# XMICRO-6502_V2_4.net
KiCad netlist of a schematic drawn in EAGLE
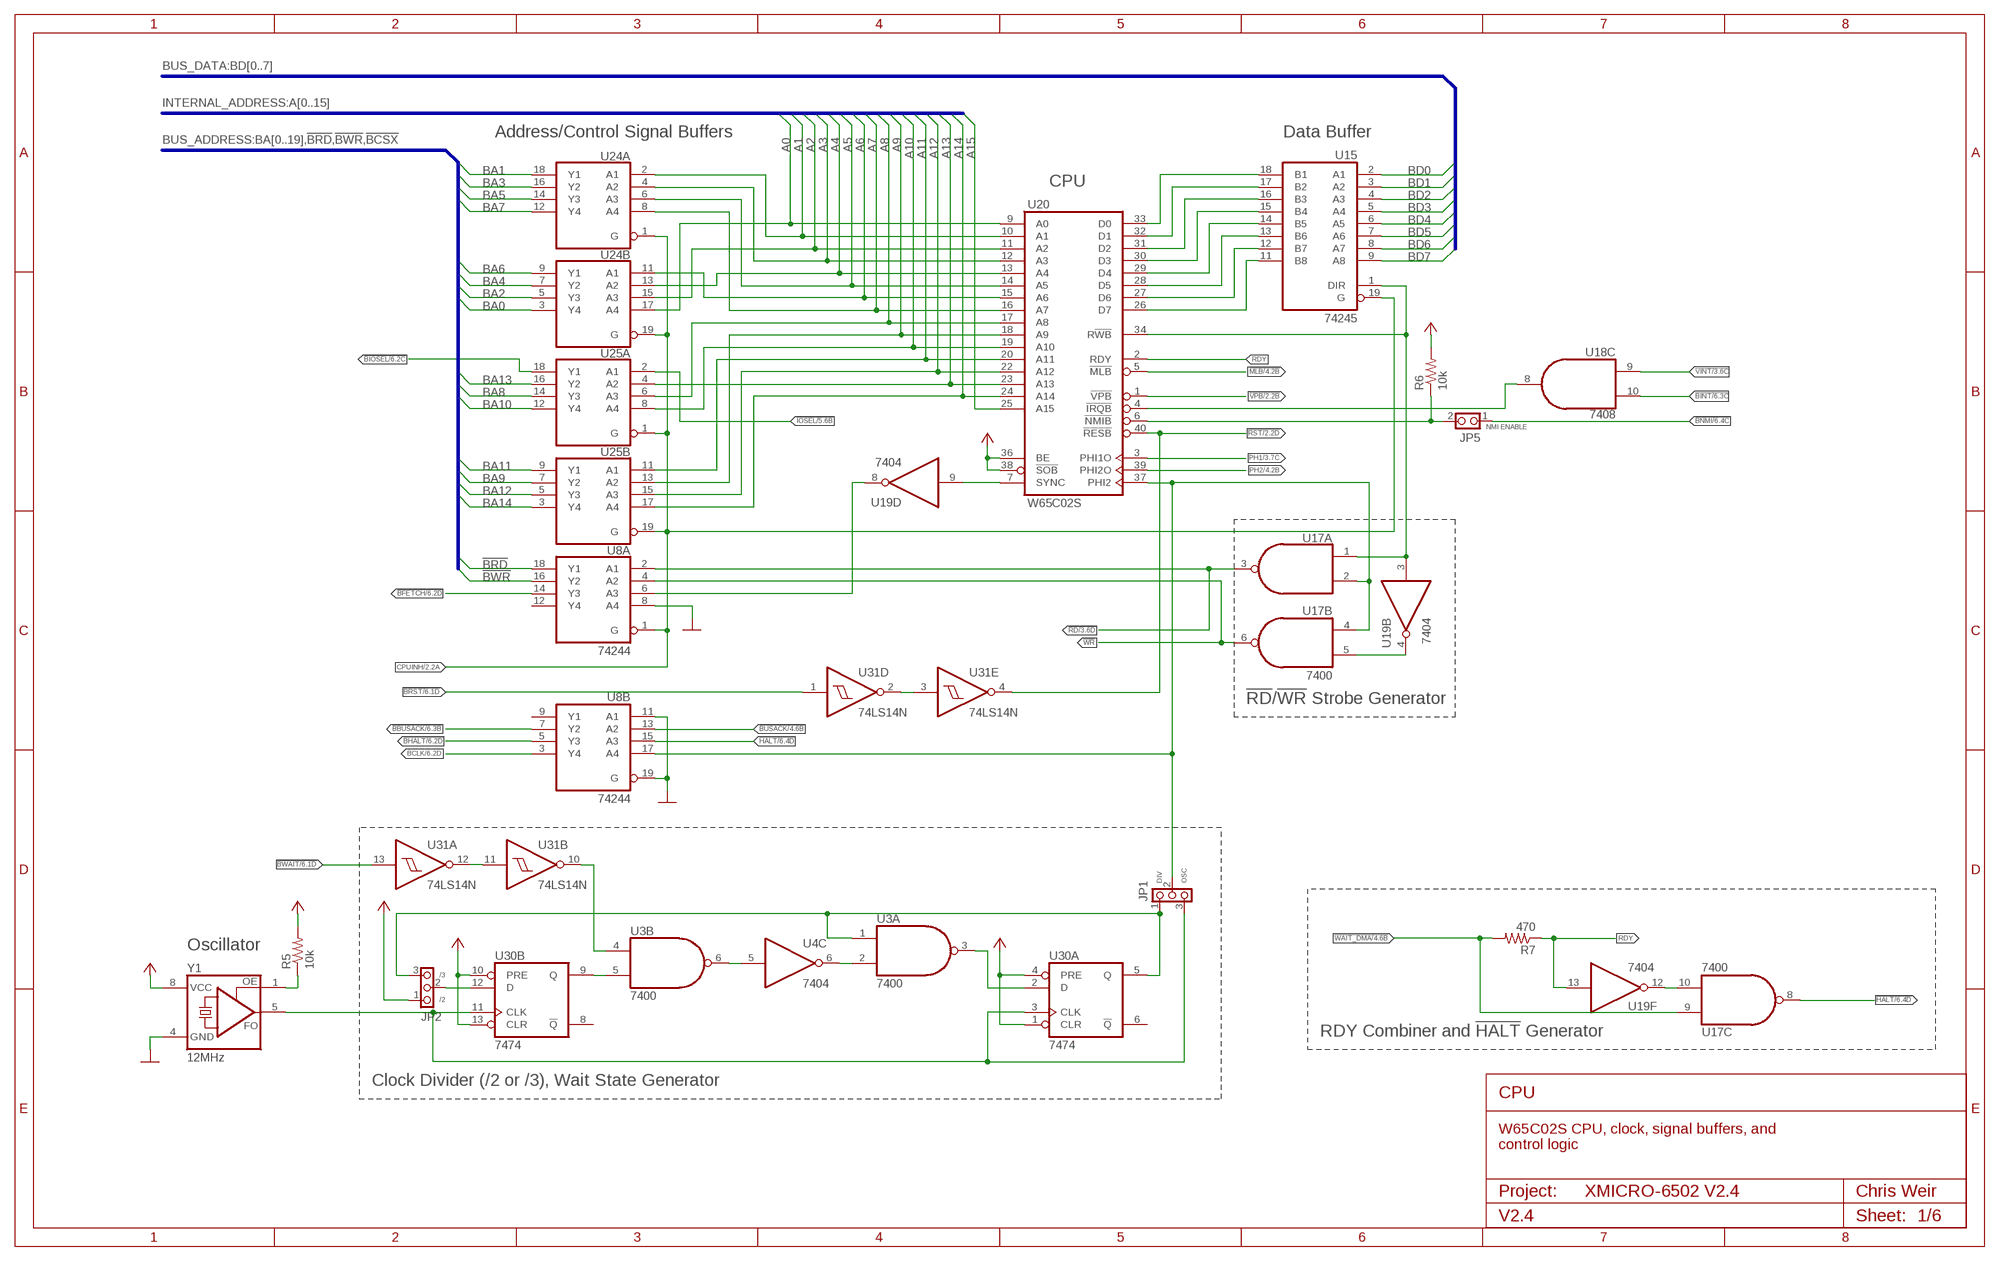
[diagram p0: schematic, sheet 1]
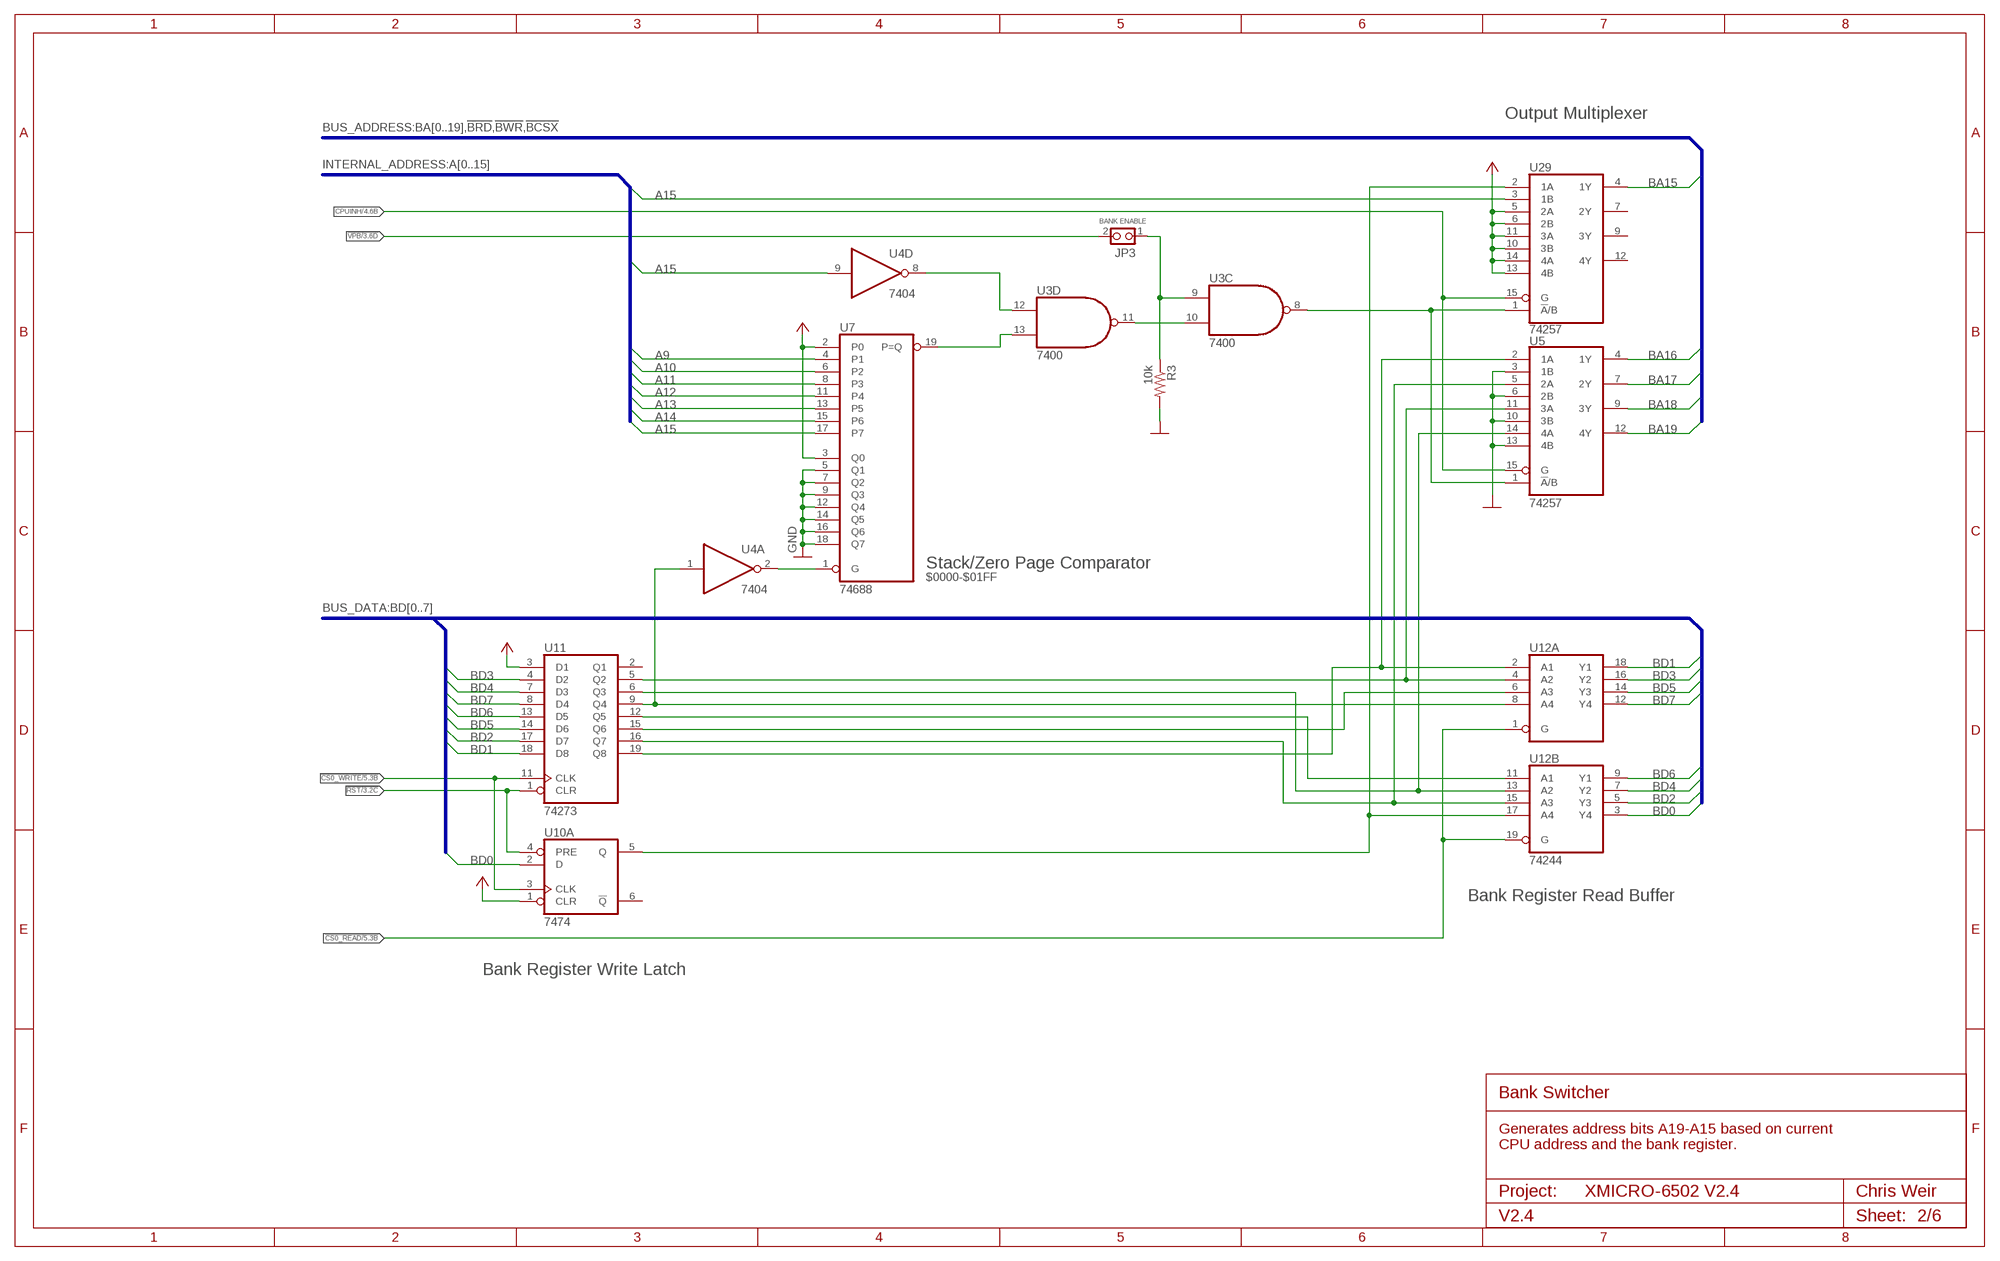
[diagram p1: schematic, sheet 2]
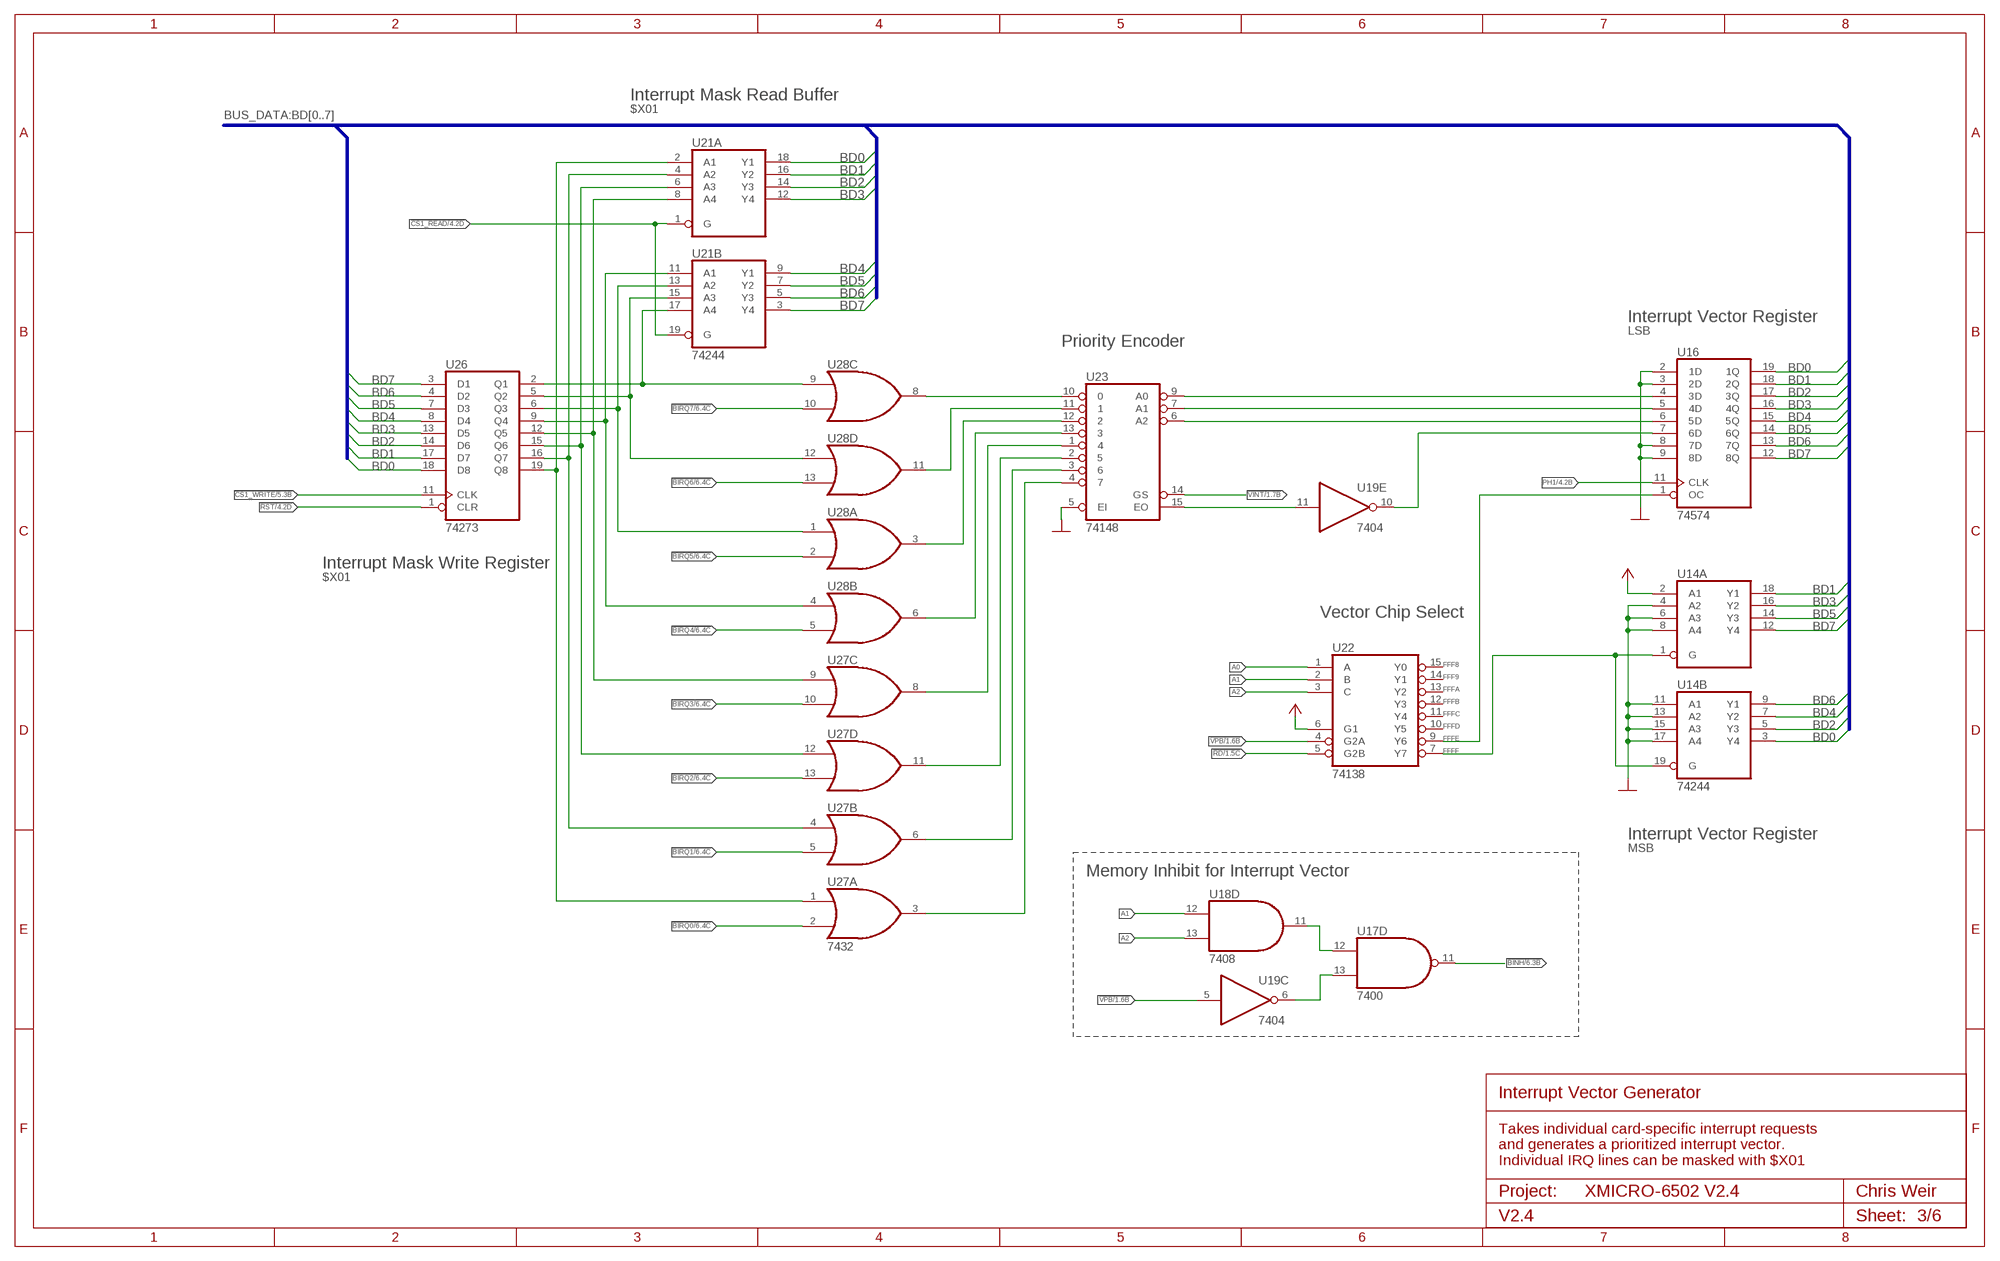
[diagram p2: schematic, sheet 3]
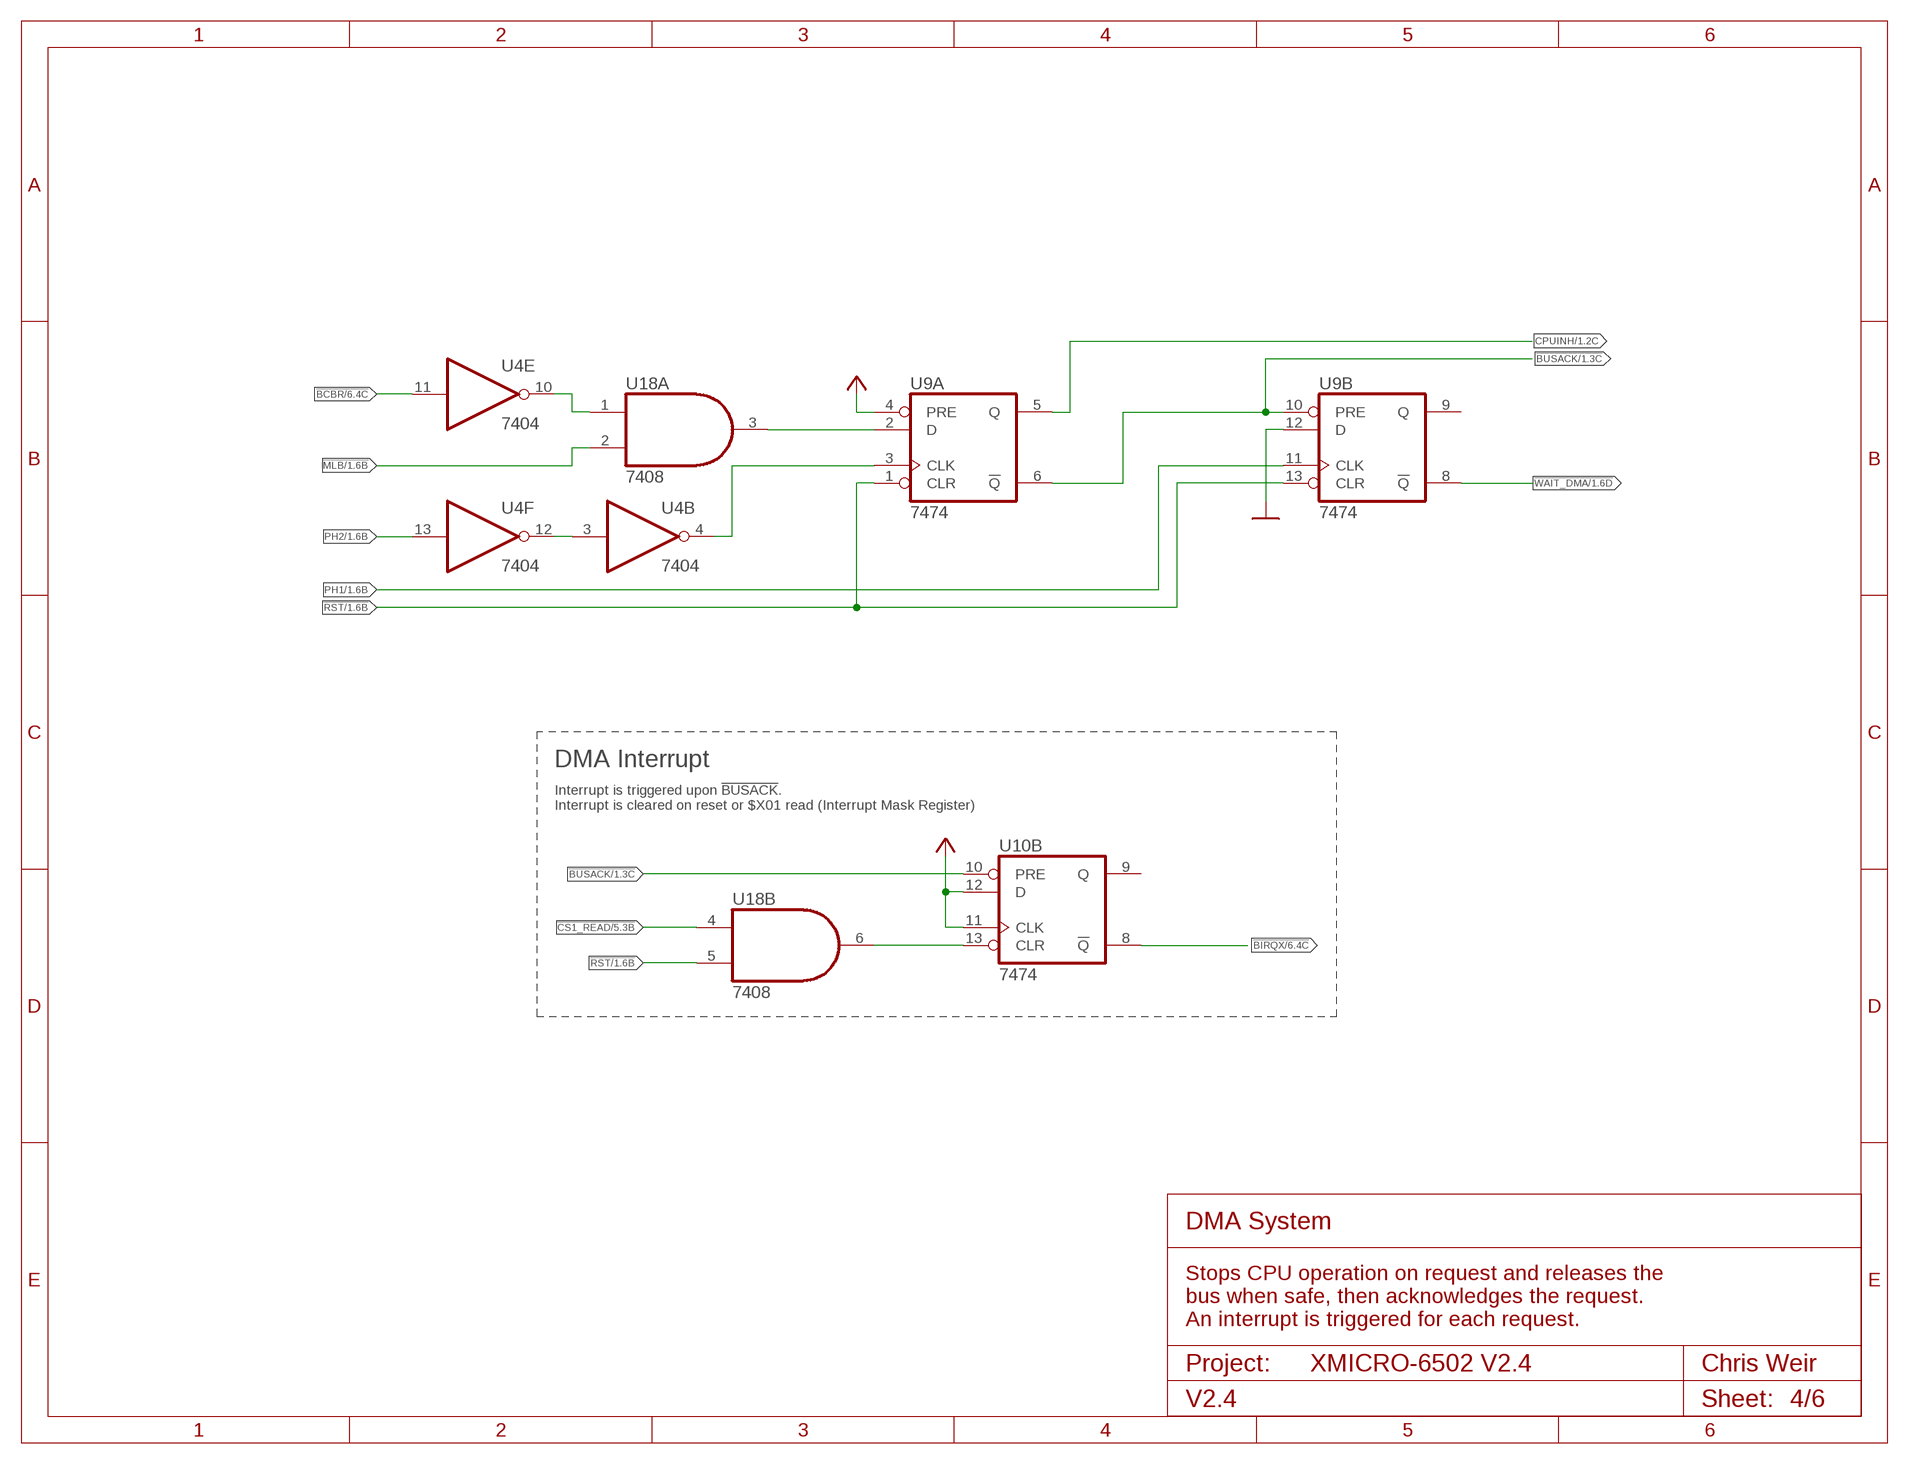
[diagram p3: schematic, sheet 4]
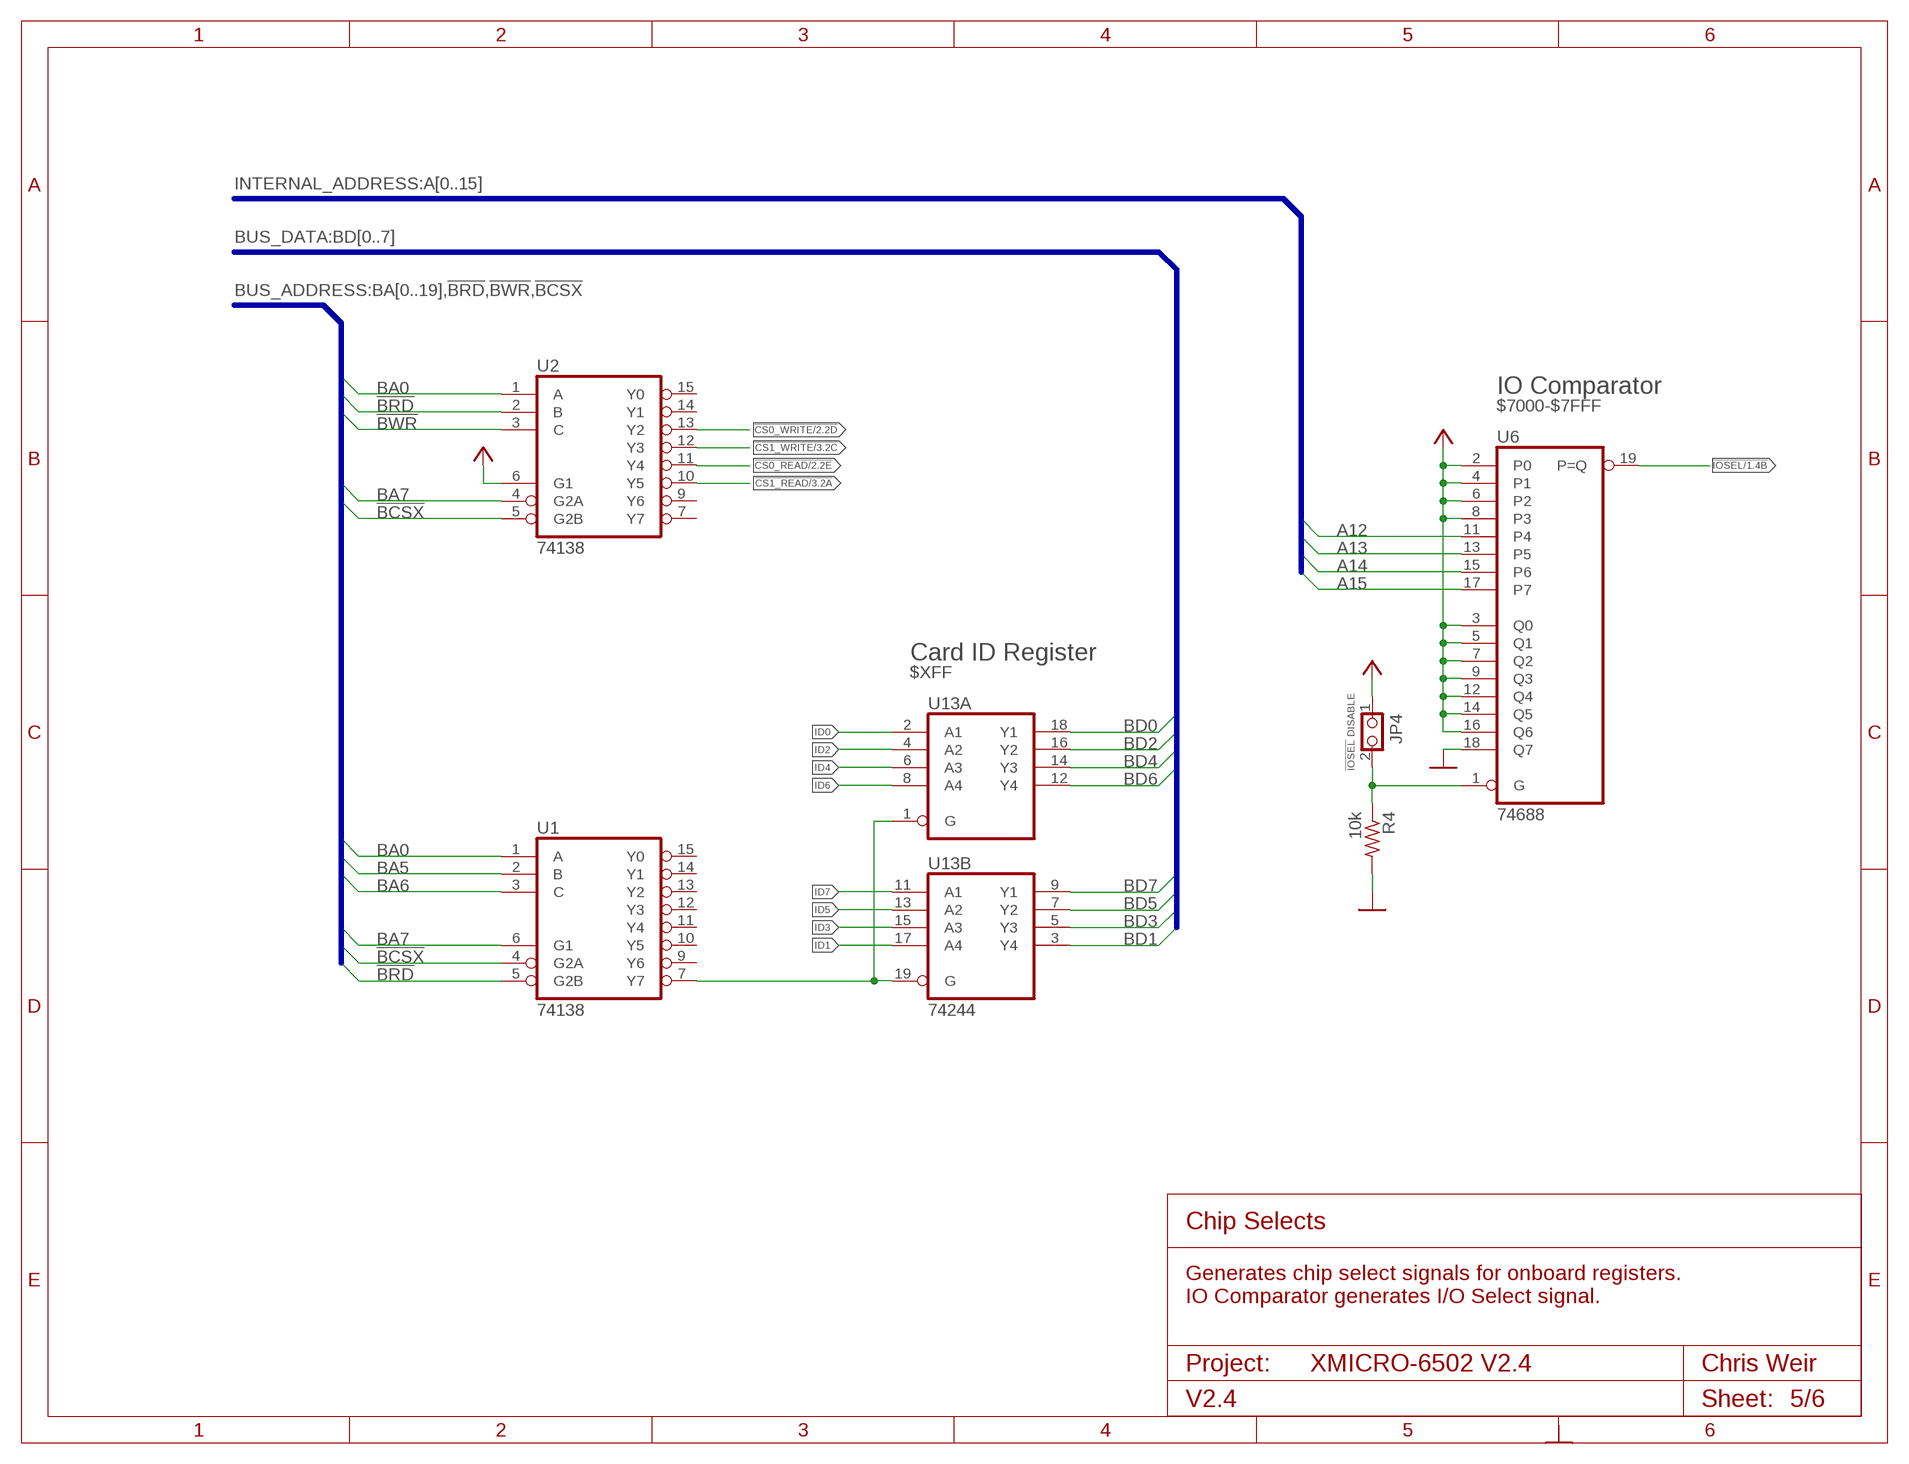
[diagram p4: schematic, sheet 5]
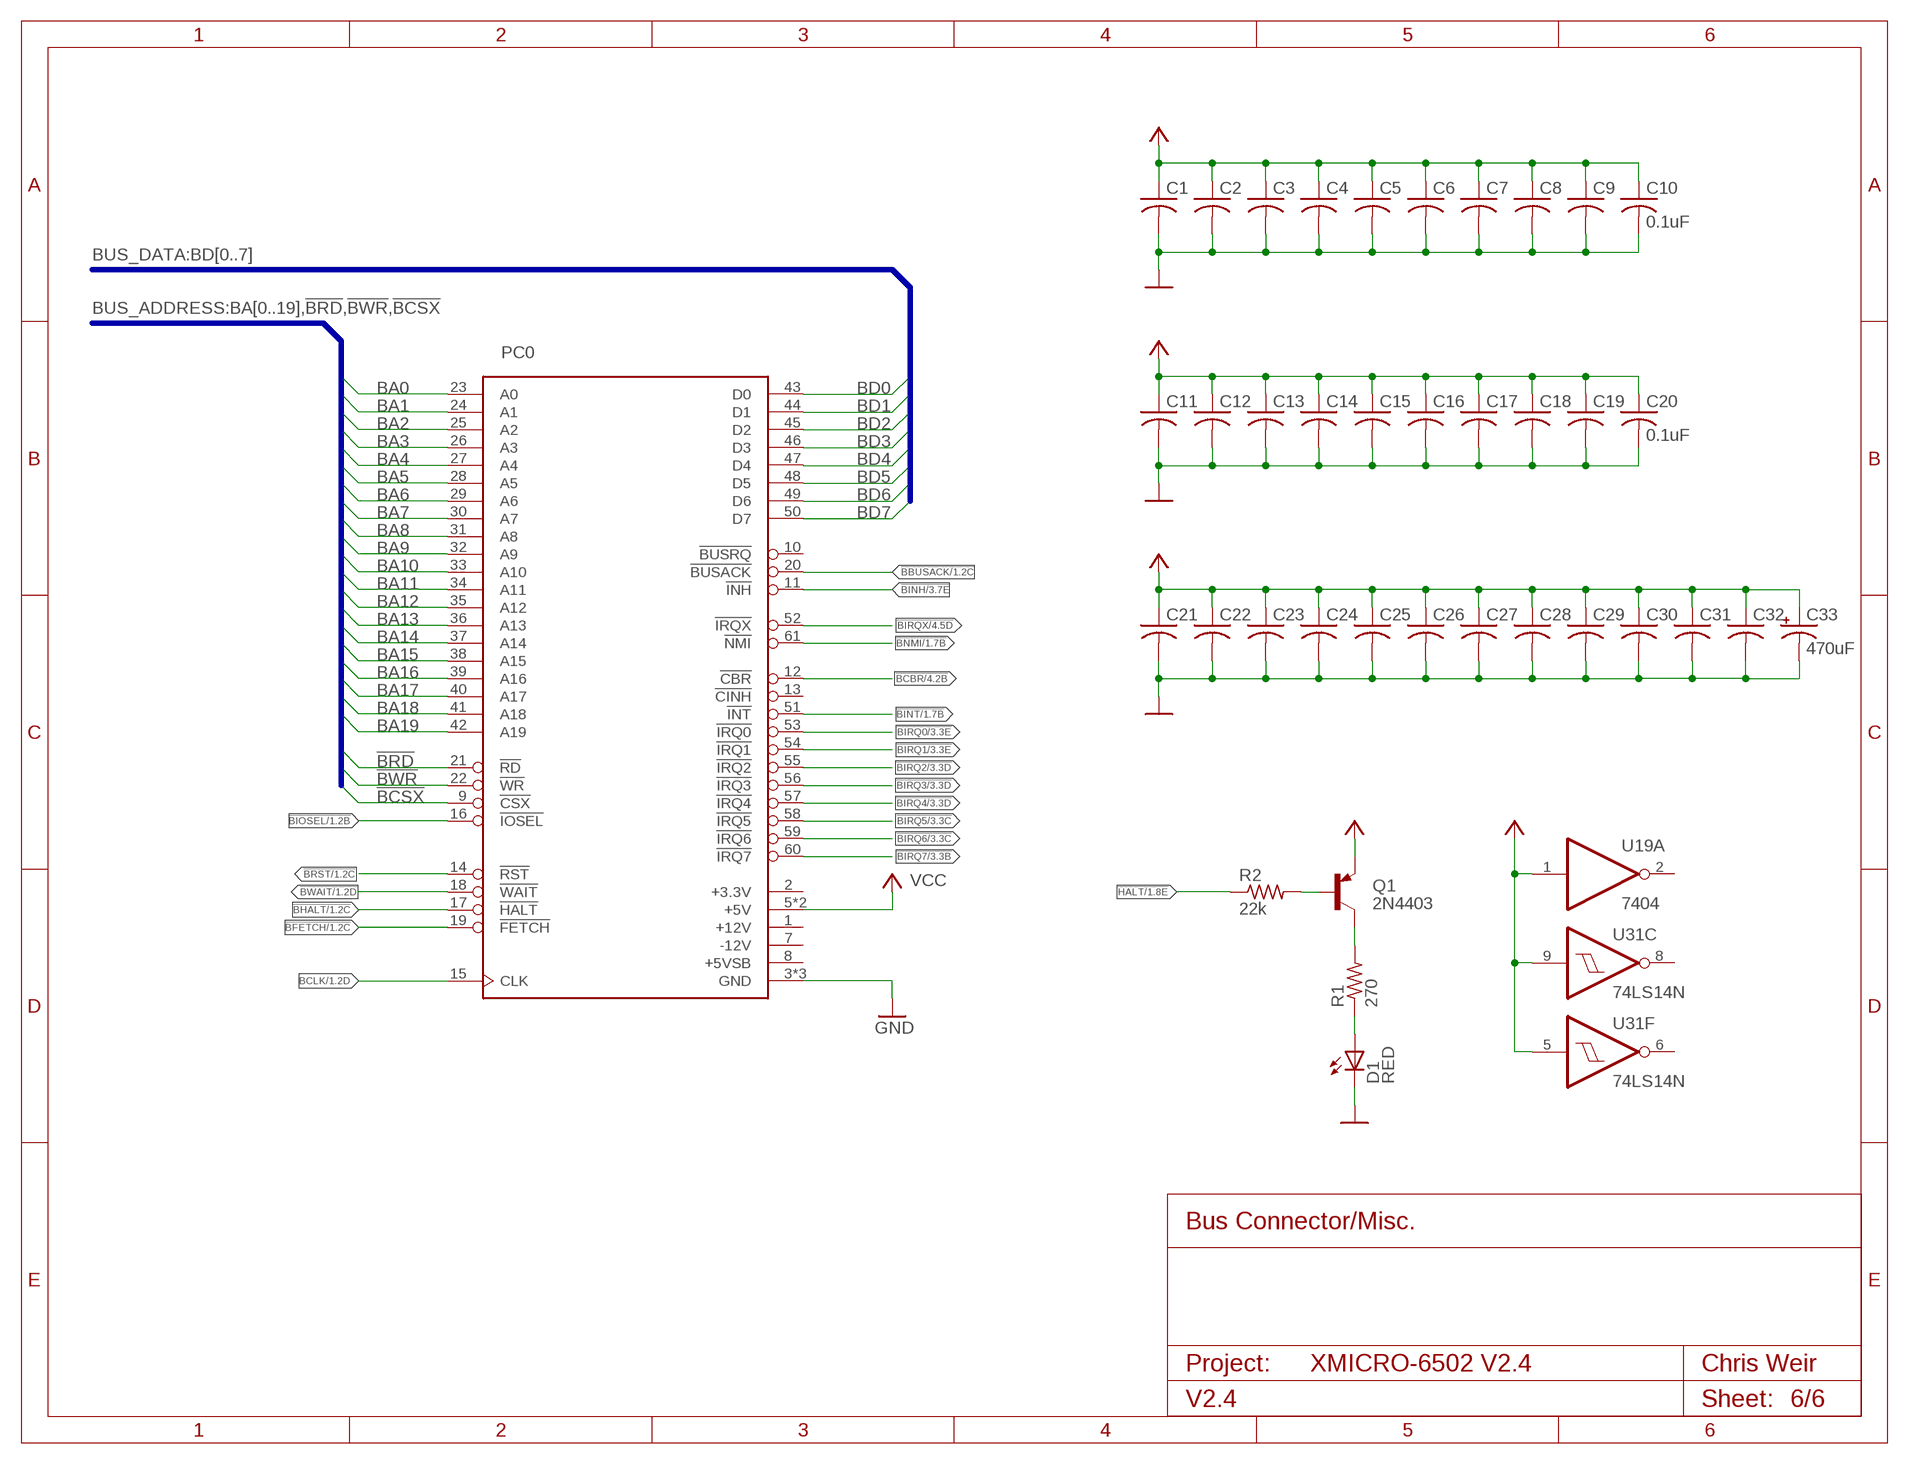
[diagram p5: schematic, sheet 6]

(export (version "E")
  (design (tool "Eeschema 10.0.6"))
  (components
    (comp (ref "C1")
      (value "0.1uF")
      (footprint "eagle-import:C025-024X044")
      (libsource (lib "eagle-import") (part "C-US025-024X044"))
    )
    (comp (ref "C2")
      (value "0.1uF")
      (footprint "eagle-import:C025-024X044")
      (libsource (lib "eagle-import") (part "C-US025-024X044"))
    )
    (comp (ref "C3")
      (value "0.1uF")
      (footprint "eagle-import:C025-024X044")
      (libsource (lib "eagle-import") (part "C-US025-024X044"))
    )
    (comp (ref "C4")
      (value "0.1uF")
      (footprint "eagle-import:C025-024X044")
      (libsource (lib "eagle-import") (part "C-US025-024X044"))
    )
    (comp (ref "C5")
      (value "0.1uF")
      (footprint "eagle-import:C025-024X044")
      (libsource (lib "eagle-import") (part "C-US025-024X044"))
    )
    (comp (ref "C6")
      (value "0.1uF")
      (footprint "eagle-import:C025-024X044")
      (libsource (lib "eagle-import") (part "C-US025-024X044"))
    )
    (comp (ref "C7")
      (value "0.1uF")
      (footprint "eagle-import:C025-024X044")
      (libsource (lib "eagle-import") (part "C-US025-024X044"))
    )
    (comp (ref "C8")
      (value "0.1uF")
      (footprint "eagle-import:C025-024X044")
      (libsource (lib "eagle-import") (part "C-US025-024X044"))
    )
    (comp (ref "C9")
      (value "0.1uF")
      (footprint "eagle-import:C025-024X044")
      (libsource (lib "eagle-import") (part "C-US025-024X044"))
    )
    (comp (ref "C10")
      (value "0.1uF")
      (footprint "eagle-import:C025-024X044")
      (libsource (lib "eagle-import") (part "C-US025-024X044"))
    )
    (comp (ref "C11")
      (value "0.1uF")
      (footprint "eagle-import:C025-024X044")
      (libsource (lib "eagle-import") (part "C-US025-024X044"))
    )
    (comp (ref "C12")
      (value "0.1uF")
      (footprint "eagle-import:C025-024X044")
      (libsource (lib "eagle-import") (part "C-US025-024X044"))
    )
    (comp (ref "C13")
      (value "0.1uF")
      (footprint "eagle-import:C025-024X044")
      (libsource (lib "eagle-import") (part "C-US025-024X044"))
    )
    (comp (ref "C14")
      (value "0.1uF")
      (footprint "eagle-import:C025-024X044")
      (libsource (lib "eagle-import") (part "C-US025-024X044"))
    )
    (comp (ref "C15")
      (value "0.1uF")
      (footprint "eagle-import:C025-024X044")
      (libsource (lib "eagle-import") (part "C-US025-024X044"))
    )
    (comp (ref "C16")
      (value "0.1uF")
      (footprint "eagle-import:C025-024X044")
      (libsource (lib "eagle-import") (part "C-US025-024X044"))
    )
    (comp (ref "C17")
      (value "0.1uF")
      (footprint "eagle-import:C025-024X044")
      (libsource (lib "eagle-import") (part "C-US025-024X044"))
    )
    (comp (ref "C18")
      (value "0.1uF")
      (footprint "eagle-import:C025-024X044")
      (libsource (lib "eagle-import") (part "C-US025-024X044"))
    )
    (comp (ref "C19")
      (value "0.1uF")
      (footprint "eagle-import:C025-024X044")
      (libsource (lib "eagle-import") (part "C-US025-024X044"))
    )
    (comp (ref "C20")
      (value "0.1uF")
      (footprint "eagle-import:C025-024X044")
      (libsource (lib "eagle-import") (part "C-US025-024X044"))
    )
    (comp (ref "C21")
      (value "0.1uF")
      (footprint "eagle-import:C025-024X044")
      (libsource (lib "eagle-import") (part "C-US025-024X044"))
    )
    (comp (ref "C22")
      (value "0.1uF")
      (footprint "eagle-import:C025-024X044")
      (libsource (lib "eagle-import") (part "C-US025-024X044"))
    )
    (comp (ref "C23")
      (value "0.1uF")
      (footprint "eagle-import:C025-024X044")
      (libsource (lib "eagle-import") (part "C-US025-024X044"))
    )
    (comp (ref "C24")
      (value "0.1uF")
      (footprint "eagle-import:C025-024X044")
      (libsource (lib "eagle-import") (part "C-US025-024X044"))
    )
    (comp (ref "C25")
      (value "0.1uF")
      (footprint "eagle-import:C025-024X044")
      (libsource (lib "eagle-import") (part "C-US025-024X044"))
    )
    (comp (ref "C26")
      (value "0.1uF")
      (footprint "eagle-import:C025-024X044")
      (libsource (lib "eagle-import") (part "C-US025-024X044"))
    )
    (comp (ref "C27")
      (value "0.1uF")
      (footprint "eagle-import:C025-024X044")
      (libsource (lib "eagle-import") (part "C-US025-024X044"))
    )
    (comp (ref "C28")
      (value "0.1uF")
      (footprint "eagle-import:C025-024X044")
      (libsource (lib "eagle-import") (part "C-US025-024X044"))
    )
    (comp (ref "C29")
      (value "0.1uF")
      (footprint "eagle-import:C025-024X044")
      (libsource (lib "eagle-import") (part "C-US025-024X044"))
    )
    (comp (ref "C30")
      (value "0.1uF")
      (footprint "eagle-import:C025-024X044")
      (libsource (lib "eagle-import") (part "C-US025-024X044"))
    )
    (comp (ref "C31")
      (value "0.1uF")
      (footprint "eagle-import:C025-024X044")
      (libsource (lib "eagle-import") (part "C-US025-024X044"))
    )
    (comp (ref "C32")
      (value "0.1uF")
      (footprint "eagle-import:C025-024X044")
      (libsource (lib "eagle-import") (part "C-US025-024X044"))
    )
    (comp (ref "C33")
      (value "470uF")
      (footprint "eagle-import:C-10-5")
      (libsource (lib "eagle-import") (part "CPOL-US-10-5"))
    )
    (comp (ref "D1")
      (value "RED")
      (footprint "eagle-import:LED5MM")
      (libsource (lib "eagle-import") (part "LED5MM"))
    )
    (comp (ref "PC0")
      (value "XMICRO-BUS-EDGE62M")
      (footprint "eagle-import:EDGE62M")
      (libsource (lib "eagle-import") (part "XMICRO-BUS-EDGE62M"))
    )
    (comp (ref "Q1")
      (value "2N4403")
      (footprint "eagle-import:TO92")
      (libsource (lib "eagle-import") (part "TRANSISTOR-PNP-2N4403"))
    )
    (comp (ref "R1")
      (value "270")
      (footprint "eagle-import:0207_10")
      (libsource (lib "eagle-import") (part "R-US_0207/10"))
    )
    (comp (ref "R2")
      (value "22k")
      (footprint "eagle-import:0207_10")
      (libsource (lib "eagle-import") (part "R-US_0207/10"))
    )
    (comp (ref "U19")
      (value "7404")
      (footprint "eagle-import:DIL14")
      (libsource (lib "eagle-import") (part "7404NLS"))
    )
    (comp (ref "U31")
      (value "74LS14N")
      (footprint "eagle-import:DIL14")
      (libsource (lib "eagle-import") (part "7414NLS"))
    )
    (comp (ref "JP3")
      (value "PINHD-1X2THRU")
      (footprint "eagle-import:1X02")
      (libsource (lib "eagle-import") (part "PINHD-1X2THRU"))
    )
    (comp (ref "R3")
      (value "10k")
      (footprint "eagle-import:0207_10")
      (libsource (lib "eagle-import") (part "R-US_0207/10"))
    )
    (comp (ref "U3")
      (value "7400")
      (footprint "eagle-import:DIL14")
      (libsource (lib "eagle-import") (part "7400NLS"))
    )
    (comp (ref "U4")
      (value "7404")
      (footprint "eagle-import:DIL14")
      (libsource (lib "eagle-import") (part "7404NLS"))
    )
    (comp (ref "U5")
      (value "74257")
      (footprint "eagle-import:DIL16")
      (libsource (lib "eagle-import") (part "74257NLS"))
    )
    (comp (ref "U7")
      (value "74688")
      (footprint "eagle-import:DIL20")
      (libsource (lib "eagle-import") (part "74688NLS"))
    )
    (comp (ref "U10")
      (value "7474")
      (footprint "eagle-import:DIL14")
      (libsource (lib "eagle-import") (part "7474NLS"))
    )
    (comp (ref "U11")
      (value "74273")
      (footprint "eagle-import:DIL20")
      (libsource (lib "eagle-import") (part "74273N"))
    )
    (comp (ref "U12")
      (value "74244")
      (footprint "eagle-import:DIL20")
      (libsource (lib "eagle-import") (part "74244NLS"))
    )
    (comp (ref "U29")
      (value "74257")
      (footprint "eagle-import:DIL16")
      (libsource (lib "eagle-import") (part "74257NLS"))
    )
    (comp (ref "JP4")
      (value "PINHD-1X2THRU")
      (footprint "eagle-import:1X02")
      (libsource (lib "eagle-import") (part "PINHD-1X2THRU"))
    )
    (comp (ref "R4")
      (value "10k")
      (footprint "eagle-import:0207_10")
      (libsource (lib "eagle-import") (part "R-US_0207/10"))
    )
    (comp (ref "U1")
      (value "74138")
      (footprint "eagle-import:DIL16")
      (libsource (lib "eagle-import") (part "74138NLS"))
    )
    (comp (ref "U2")
      (value "74138")
      (footprint "eagle-import:DIL16")
      (libsource (lib "eagle-import") (part "74138NLS"))
    )
    (comp (ref "U6")
      (value "74688")
      (footprint "eagle-import:DIL20")
      (libsource (lib "eagle-import") (part "74688NLS"))
    )
    (comp (ref "U13")
      (value "74244")
      (footprint "eagle-import:DIL20")
      (libsource (lib "eagle-import") (part "74244NLS"))
    )
    (comp (ref "U14")
      (value "74244")
      (footprint "eagle-import:DIL20")
      (libsource (lib "eagle-import") (part "74244NLS"))
    )
    (comp (ref "U16")
      (value "74574")
      (footprint "eagle-import:DIL20")
      (libsource (lib "eagle-import") (part "74574NHC"))
    )
    (comp (ref "U17")
      (value "7400")
      (footprint "eagle-import:DIL14")
      (libsource (lib "eagle-import") (part "7400NLS"))
    )
    (comp (ref "U18")
      (value "7408")
      (footprint "eagle-import:DIL14")
      (libsource (lib "eagle-import") (part "7408NLS"))
    )
    (comp (ref "U21")
      (value "74244")
      (footprint "eagle-import:DIL20")
      (libsource (lib "eagle-import") (part "74244NLS"))
    )
    (comp (ref "U22")
      (value "74138")
      (footprint "eagle-import:DIL16")
      (libsource (lib "eagle-import") (part "74138NLS"))
    )
    (comp (ref "U23")
      (value "74148")
      (footprint "eagle-import:DIL16")
      (libsource (lib "eagle-import") (part "74148NLS"))
    )
    (comp (ref "U26")
      (value "74273")
      (footprint "eagle-import:DIL20")
      (libsource (lib "eagle-import") (part "74273N"))
    )
    (comp (ref "U27")
      (value "7432")
      (footprint "eagle-import:DIL14")
      (libsource (lib "eagle-import") (part "7432NLS"))
    )
    (comp (ref "U28")
      (value "7432")
      (footprint "eagle-import:DIL14")
      (libsource (lib "eagle-import") (part "7432NLS"))
    )
    (comp (ref "U9")
      (value "7474")
      (footprint "eagle-import:DIL14")
      (libsource (lib "eagle-import") (part "7474NLS"))
    )
    (comp (ref "JP1")
      (value "PINHD1X3THRU")
      (footprint "eagle-import:1X03")
      (libsource (lib "eagle-import") (part "PINHD1X3THRU"))
    )
    (comp (ref "JP2")
      (value "PINHD1X3THRU")
      (footprint "eagle-import:1X03")
      (libsource (lib "eagle-import") (part "PINHD1X3THRU"))
    )
    (comp (ref "JP5")
      (value "PINHD-1X2THRU")
      (footprint "eagle-import:1X02")
      (libsource (lib "eagle-import") (part "PINHD-1X2THRU"))
    )
    (comp (ref "R5")
      (value "10k")
      (footprint "eagle-import:0207_10")
      (libsource (lib "eagle-import") (part "R-US_0207/10"))
    )
    (comp (ref "R6")
      (value "10k")
      (footprint "eagle-import:0207_10")
      (libsource (lib "eagle-import") (part "R-US_0207/10"))
    )
    (comp (ref "R7")
      (value "470")
      (footprint "eagle-import:0207_10")
      (libsource (lib "eagle-import") (part "R-US_0207/10"))
    )
    (comp (ref "U8")
      (value "74244")
      (footprint "eagle-import:DIL20")
      (libsource (lib "eagle-import") (part "74244NLS"))
    )
    (comp (ref "U15")
      (value "74245")
      (footprint "eagle-import:DIL20")
      (libsource (lib "eagle-import") (part "74245NLS"))
    )
    (comp (ref "U20")
      (value "W65C02S")
      (footprint "eagle-import:DIL40")
      (libsource (lib "eagle-import") (part "W65C02P"))
    )
    (comp (ref "U24")
      (value "74244")
      (footprint "eagle-import:DIL20")
      (libsource (lib "eagle-import") (part "74244NLS"))
    )
    (comp (ref "U25")
      (value "74244")
      (footprint "eagle-import:DIL20")
      (libsource (lib "eagle-import") (part "74244NLS"))
    )
    (comp (ref "U30")
      (value "7474")
      (footprint "eagle-import:DIL14")
      (libsource (lib "eagle-import") (part "7474NLS"))
    )
    (comp (ref "Y1")
      (value "12MHz")
      (footprint "eagle-import:DIL08S")
      (libsource (lib "eagle-import") (part "OSC-OE"))
    )
  )
  (nets
    (net (code "105") (name "A0") (class "Default")
      (node (ref "U20") (pin "9") (pinfunction "A0_9") (pintype "output"))
      (node (ref "U22") (pin "1") (pinfunction "A_1") (pintype "input"))
      (node (ref "U24") (pin "17") (pinfunction "A4_17") (pintype "input"))
    )
    (net (code "106") (name "A1") (class "Default")
      (node (ref "U18") (pin "12") (pinfunction "I0_12") (pintype "input"))
      (node (ref "U20") (pin "10") (pinfunction "A1_10") (pintype "output"))
      (node (ref "U22") (pin "2") (pinfunction "B_2") (pintype "input"))
      (node (ref "U24") (pin "2") (pinfunction "A1_2") (pintype "input"))
    )
    (net (code "107") (name "A2") (class "Default")
      (node (ref "U18") (pin "13") (pinfunction "I1_13") (pintype "input"))
      (node (ref "U20") (pin "11") (pinfunction "A2_11") (pintype "output"))
      (node (ref "U22") (pin "3") (pinfunction "C_3") (pintype "input"))
      (node (ref "U24") (pin "15") (pinfunction "A3_15") (pintype "input"))
    )
    (net (code "108") (name "A3") (class "Default")
      (node (ref "U20") (pin "12") (pinfunction "A3_12") (pintype "output"))
      (node (ref "U24") (pin "4") (pinfunction "A2_4") (pintype "input"))
    )
    (net (code "109") (name "A4") (class "Default")
      (node (ref "U20") (pin "13") (pinfunction "A4_13") (pintype "output"))
      (node (ref "U24") (pin "13") (pinfunction "A2_13") (pintype "input"))
    )
    (net (code "110") (name "A5") (class "Default")
      (node (ref "U20") (pin "14") (pinfunction "A5_14") (pintype "output"))
      (node (ref "U24") (pin "6") (pinfunction "A3_6") (pintype "input"))
    )
    (net (code "111") (name "A6") (class "Default")
      (node (ref "U20") (pin "15") (pinfunction "A6_15") (pintype "output"))
      (node (ref "U24") (pin "11") (pinfunction "A1_11") (pintype "input"))
    )
    (net (code "112") (name "A7") (class "Default")
      (node (ref "U20") (pin "16") (pinfunction "A7_16") (pintype "output"))
      (node (ref "U24") (pin "8") (pinfunction "A4_8") (pintype "input"))
    )
    (net (code "113") (name "A8") (class "Default")
      (node (ref "U20") (pin "17") (pinfunction "A8_17") (pintype "output"))
      (node (ref "U25") (pin "6") (pinfunction "A3_6") (pintype "input"))
    )
    (net (code "114") (name "A9") (class "Default")
      (node (ref "U20") (pin "18") (pinfunction "A9_18") (pintype "output"))
      (node (ref "U25") (pin "13") (pinfunction "A2_13") (pintype "input"))
      (node (ref "U7") (pin "4") (pinfunction "P1_4") (pintype "input"))
    )
    (net (code "115") (name "A10") (class "Default")
      (node (ref "U20") (pin "19") (pinfunction "A10_19") (pintype "output"))
      (node (ref "U25") (pin "8") (pinfunction "A4_8") (pintype "input"))
      (node (ref "U7") (pin "6") (pinfunction "P2_6") (pintype "input"))
    )
    (net (code "116") (name "A11") (class "Default")
      (node (ref "U20") (pin "20") (pinfunction "A11_20") (pintype "output"))
      (node (ref "U25") (pin "11") (pinfunction "A1_11") (pintype "input"))
      (node (ref "U7") (pin "8") (pinfunction "P3_8") (pintype "input"))
    )
    (net (code "117") (name "A12") (class "Default")
      (node (ref "U20") (pin "22") (pinfunction "A12_22") (pintype "output"))
      (node (ref "U25") (pin "15") (pinfunction "A3_15") (pintype "input"))
      (node (ref "U6") (pin "11") (pinfunction "P4_11") (pintype "input"))
      (node (ref "U7") (pin "11") (pinfunction "P4_11") (pintype "input"))
    )
    (net (code "118") (name "A13") (class "Default")
      (node (ref "U20") (pin "23") (pinfunction "A13_23") (pintype "output"))
      (node (ref "U25") (pin "4") (pinfunction "A2_4") (pintype "input"))
      (node (ref "U6") (pin "13") (pinfunction "P5_13") (pintype "input"))
      (node (ref "U7") (pin "13") (pinfunction "P5_13") (pintype "input"))
    )
    (net (code "119") (name "A14") (class "Default")
      (node (ref "U20") (pin "24") (pinfunction "A14_24") (pintype "output"))
      (node (ref "U25") (pin "17") (pinfunction "A4_17") (pintype "input"))
      (node (ref "U6") (pin "15") (pinfunction "P6_15") (pintype "input"))
      (node (ref "U7") (pin "15") (pinfunction "P6_15") (pintype "input"))
    )
    (net (code "120") (name "A15") (class "Default")
      (node (ref "U20") (pin "25") (pinfunction "A15_25") (pintype "output"))
      (node (ref "U29") (pin "3") (pinfunction "1B_3") (pintype "input"))
      (node (ref "U4") (pin "9") (pinfunction "I_9") (pintype "input"))
      (node (ref "U6") (pin "17") (pinfunction "P7_17") (pintype "input"))
      (node (ref "U7") (pin "17") (pinfunction "P7_17") (pintype "input"))
    )
    (net (code "121") (name "BA0") (class "Default")
      (node (ref "PC0") (pin "23") (pinfunction "A0_23") (pintype "bidirectional"))
      (node (ref "U1") (pin "1") (pinfunction "A_1") (pintype "input"))
      (node (ref "U2") (pin "1") (pinfunction "A_1") (pintype "input"))
      (node (ref "U24") (pin "3") (pinfunction "Y4_3") (pintype "tri_state"))
    )
    (net (code "122") (name "BA1") (class "Default")
      (node (ref "PC0") (pin "24") (pinfunction "A1_24") (pintype "bidirectional"))
      (node (ref "U24") (pin "18") (pinfunction "Y1_18") (pintype "tri_state"))
    )
    (net (code "123") (name "BA2") (class "Default")
      (node (ref "PC0") (pin "25") (pinfunction "A2_25") (pintype "bidirectional"))
      (node (ref "U24") (pin "5") (pinfunction "Y3_5") (pintype "tri_state"))
    )
    (net (code "124") (name "BA3") (class "Default")
      (node (ref "PC0") (pin "26") (pinfunction "A3_26") (pintype "bidirectional"))
      (node (ref "U24") (pin "16") (pinfunction "Y2_16") (pintype "tri_state"))
    )
    (net (code "125") (name "BA4") (class "Default")
      (node (ref "PC0") (pin "27") (pinfunction "A4_27") (pintype "bidirectional"))
      (node (ref "U24") (pin "7") (pinfunction "Y2_7") (pintype "tri_state"))
    )
    (net (code "126") (name "BA5") (class "Default")
      (node (ref "PC0") (pin "28") (pinfunction "A5_28") (pintype "bidirectional"))
      (node (ref "U1") (pin "2") (pinfunction "B_2") (pintype "input"))
      (node (ref "U24") (pin "14") (pinfunction "Y3_14") (pintype "tri_state"))
    )
    (net (code "127") (name "BA6") (class "Default")
      (node (ref "PC0") (pin "29") (pinfunction "A6_29") (pintype "bidirectional"))
      (node (ref "U1") (pin "3") (pinfunction "C_3") (pintype "input"))
      (node (ref "U24") (pin "9") (pinfunction "Y1_9") (pintype "tri_state"))
    )
    (net (code "128") (name "BA7") (class "Default")
      (node (ref "PC0") (pin "30") (pinfunction "A7_30") (pintype "bidirectional"))
      (node (ref "U1") (pin "6") (pinfunction "G1_6") (pintype "input"))
      (node (ref "U2") (pin "4") (pinfunction "G2A_4") (pintype "input"))
      (node (ref "U24") (pin "12") (pinfunction "Y4_12") (pintype "tri_state"))
    )
    (net (code "129") (name "BA8") (class "Default")
      (node (ref "PC0") (pin "31") (pinfunction "A8_31") (pintype "bidirectional"))
      (node (ref "U25") (pin "14") (pinfunction "Y3_14") (pintype "tri_state"))
    )
    (net (code "130") (name "BA9") (class "Default")
      (node (ref "PC0") (pin "32") (pinfunction "A9_32") (pintype "bidirectional"))
      (node (ref "U25") (pin "7") (pinfunction "Y2_7") (pintype "tri_state"))
    )
    (net (code "131") (name "BA10") (class "Default")
      (node (ref "PC0") (pin "33") (pinfunction "A10_33") (pintype "bidirectional"))
      (node (ref "U25") (pin "12") (pinfunction "Y4_12") (pintype "tri_state"))
    )
    (net (code "132") (name "BA11") (class "Default")
      (node (ref "PC0") (pin "34") (pinfunction "A11_34") (pintype "bidirectional"))
      (node (ref "U25") (pin "9") (pinfunction "Y1_9") (pintype "tri_state"))
    )
    (net (code "133") (name "BA12") (class "Default")
      (node (ref "PC0") (pin "35") (pinfunction "A12_35") (pintype "bidirectional"))
      (node (ref "U25") (pin "5") (pinfunction "Y3_5") (pintype "tri_state"))
    )
    (net (code "134") (name "BA13") (class "Default")
      (node (ref "PC0") (pin "36") (pinfunction "A13_36") (pintype "bidirectional"))
      (node (ref "U25") (pin "16") (pinfunction "Y2_16") (pintype "tri_state"))
    )
    (net (code "135") (name "BA14") (class "Default")
      (node (ref "PC0") (pin "37") (pinfunction "A14_37") (pintype "bidirectional"))
      (node (ref "U25") (pin "3") (pinfunction "Y4_3") (pintype "tri_state"))
    )
    (net (code "136") (name "BA15") (class "Default")
      (node (ref "PC0") (pin "38") (pinfunction "A15_38") (pintype "bidirectional"))
      (node (ref "U29") (pin "4") (pinfunction "1Y_4") (pintype "tri_state"))
    )
    (net (code "137") (name "BA16") (class "Default")
      (node (ref "PC0") (pin "39") (pinfunction "A16_39") (pintype "bidirectional"))
      (node (ref "U5") (pin "4") (pinfunction "1Y_4") (pintype "tri_state"))
    )
    (net (code "138") (name "BA17") (class "Default")
      (node (ref "PC0") (pin "40") (pinfunction "A17_40") (pintype "bidirectional"))
      (node (ref "U5") (pin "7") (pinfunction "2Y_7") (pintype "tri_state"))
    )
    (net (code "139") (name "BA18") (class "Default")
      (node (ref "PC0") (pin "41") (pinfunction "A18_41") (pintype "bidirectional"))
      (node (ref "U5") (pin "9") (pinfunction "3Y_9") (pintype "tri_state"))
    )
    (net (code "140") (name "BA19") (class "Default")
      (node (ref "PC0") (pin "42") (pinfunction "A19_42") (pintype "bidirectional"))
      (node (ref "U5") (pin "12") (pinfunction "4Y_12") (pintype "tri_state"))
    )
    (net (code "141") (name "BCLK") (class "Default")
      (node (ref "PC0") (pin "15") (pinfunction "CLK_15") (pintype "bidirectional"))
      (node (ref "U8") (pin "3") (pinfunction "Y4_3") (pintype "tri_state"))
    )
    (net (code "142") (name "BD0") (class "Default")
      (node (ref "PC0") (pin "43") (pinfunction "D0_43") (pintype "bidirectional"))
      (node (ref "U10") (pin "2") (pinfunction "D_2") (pintype "input"))
      (node (ref "U12") (pin "3") (pinfunction "Y4_3") (pintype "tri_state"))
      (node (ref "U13") (pin "18") (pinfunction "Y1_18") (pintype "tri_state"))
      (node (ref "U14") (pin "3") (pinfunction "Y4_3") (pintype "tri_state"))
      (node (ref "U15") (pin "2") (pinfunction "A1_2") (pintype "bidirectional"))
      (node (ref "U16") (pin "19") (pinfunction "1Q_19") (pintype "tri_state"))
      (node (ref "U21") (pin "18") (pinfunction "Y1_18") (pintype "tri_state"))
      (node (ref "U26") (pin "18") (pinfunction "D8_18") (pintype "input"))
    )
    (net (code "143") (name "BD1") (class "Default")
      (node (ref "PC0") (pin "44") (pinfunction "D1_44") (pintype "bidirectional"))
      (node (ref "U11") (pin "18") (pinfunction "D8_18") (pintype "input"))
      (node (ref "U12") (pin "18") (pinfunction "Y1_18") (pintype "tri_state"))
      (node (ref "U13") (pin "3") (pinfunction "Y4_3") (pintype "tri_state"))
      (node (ref "U14") (pin "18") (pinfunction "Y1_18") (pintype "tri_state"))
      (node (ref "U15") (pin "3") (pinfunction "A2_3") (pintype "bidirectional"))
      (node (ref "U16") (pin "18") (pinfunction "2Q_18") (pintype "tri_state"))
      (node (ref "U21") (pin "16") (pinfunction "Y2_16") (pintype "tri_state"))
      (node (ref "U26") (pin "17") (pinfunction "D7_17") (pintype "input"))
    )
    (net (code "144") (name "BD2") (class "Default")
      (node (ref "PC0") (pin "45") (pinfunction "D2_45") (pintype "bidirectional"))
      (node (ref "U11") (pin "17") (pinfunction "D7_17") (pintype "input"))
      (node (ref "U12") (pin "5") (pinfunction "Y3_5") (pintype "tri_state"))
      (node (ref "U13") (pin "16") (pinfunction "Y2_16") (pintype "tri_state"))
      (node (ref "U14") (pin "5") (pinfunction "Y3_5") (pintype "tri_state"))
      (node (ref "U15") (pin "4") (pinfunction "A3_4") (pintype "bidirectional"))
      (node (ref "U16") (pin "17") (pinfunction "3Q_17") (pintype "tri_state"))
      (node (ref "U21") (pin "14") (pinfunction "Y3_14") (pintype "tri_state"))
      (node (ref "U26") (pin "14") (pinfunction "D6_14") (pintype "input"))
    )
    (net (code "145") (name "BD3") (class "Default")
      (node (ref "PC0") (pin "46") (pinfunction "D3_46") (pintype "bidirectional"))
      (node (ref "U11") (pin "4") (pinfunction "D2_4") (pintype "input"))
      (node (ref "U12") (pin "16") (pinfunction "Y2_16") (pintype "tri_state"))
      (node (ref "U13") (pin "5") (pinfunction "Y3_5") (pintype "tri_state"))
      (node (ref "U14") (pin "16") (pinfunction "Y2_16") (pintype "tri_state"))
      (node (ref "U15") (pin "5") (pinfunction "A4_5") (pintype "bidirectional"))
      (node (ref "U16") (pin "16") (pinfunction "4Q_16") (pintype "tri_state"))
      (node (ref "U21") (pin "12") (pinfunction "Y4_12") (pintype "tri_state"))
      (node (ref "U26") (pin "13") (pinfunction "D5_13") (pintype "input"))
    )
    (net (code "146") (name "BD4") (class "Default")
      (node (ref "PC0") (pin "47") (pinfunction "D4_47") (pintype "bidirectional"))
      (node (ref "U11") (pin "7") (pinfunction "D3_7") (pintype "input"))
      (node (ref "U12") (pin "7") (pinfunction "Y2_7") (pintype "tri_state"))
      (node (ref "U13") (pin "14") (pinfunction "Y3_14") (pintype "tri_state"))
      (node (ref "U14") (pin "7") (pinfunction "Y2_7") (pintype "tri_state"))
      (node (ref "U15") (pin "6") (pinfunction "A5_6") (pintype "bidirectional"))
      (node (ref "U16") (pin "15") (pinfunction "5Q_15") (pintype "tri_state"))
      (node (ref "U21") (pin "9") (pinfunction "Y1_9") (pintype "tri_state"))
      (node (ref "U26") (pin "8") (pinfunction "D4_8") (pintype "input"))
    )
    (net (code "147") (name "BD5") (class "Default")
      (node (ref "PC0") (pin "48") (pinfunction "D5_48") (pintype "bidirectional"))
      (node (ref "U11") (pin "14") (pinfunction "D6_14") (pintype "input"))
      (node (ref "U12") (pin "14") (pinfunction "Y3_14") (pintype "tri_state"))
      (node (ref "U13") (pin "7") (pinfunction "Y2_7") (pintype "tri_state"))
      (node (ref "U14") (pin "14") (pinfunction "Y3_14") (pintype "tri_state"))
      (node (ref "U15") (pin "7") (pinfunction "A6_7") (pintype "bidirectional"))
      (node (ref "U16") (pin "14") (pinfunction "6Q_14") (pintype "tri_state"))
      (node (ref "U21") (pin "7") (pinfunction "Y2_7") (pintype "tri_state"))
      (node (ref "U26") (pin "7") (pinfunction "D3_7") (pintype "input"))
    )
    (net (code "148") (name "BD6") (class "Default")
      (node (ref "PC0") (pin "49") (pinfunction "D6_49") (pintype "bidirectional"))
      (node (ref "U11") (pin "13") (pinfunction "D5_13") (pintype "input"))
      (node (ref "U12") (pin "9") (pinfunction "Y1_9") (pintype "tri_state"))
      (node (ref "U13") (pin "12") (pinfunction "Y4_12") (pintype "tri_state"))
      (node (ref "U14") (pin "9") (pinfunction "Y1_9") (pintype "tri_state"))
      (node (ref "U15") (pin "8") (pinfunction "A7_8") (pintype "bidirectional"))
      (node (ref "U16") (pin "13") (pinfunction "7Q_13") (pintype "tri_state"))
      (node (ref "U21") (pin "5") (pinfunction "Y3_5") (pintype "tri_state"))
      (node (ref "U26") (pin "4") (pinfunction "D2_4") (pintype "input"))
    )
    (net (code "149") (name "BD7") (class "Default")
      (node (ref "PC0") (pin "50") (pinfunction "D7_50") (pintype "bidirectional"))
      (node (ref "U11") (pin "8") (pinfunction "D4_8") (pintype "input"))
      (node (ref "U12") (pin "12") (pinfunction "Y4_12") (pintype "tri_state"))
      (node (ref "U13") (pin "9") (pinfunction "Y1_9") (pintype "tri_state"))
      (node (ref "U14") (pin "12") (pinfunction "Y4_12") (pintype "tri_state"))
      (node (ref "U15") (pin "9") (pinfunction "A8_9") (pintype "bidirectional"))
      (node (ref "U16") (pin "12") (pinfunction "8Q_12") (pintype "tri_state"))
      (node (ref "U21") (pin "3") (pinfunction "Y4_3") (pintype "tri_state"))
      (node (ref "U26") (pin "3") (pinfunction "D1_3") (pintype "input"))
    )
    (net (code "150") (name "CPUINH") (class "Default")
      (node (ref "U15") (pin "19") (pinfunction "G_19") (pintype "input"))
      (node (ref "U24") (pin "1") (pinfunction "G_1") (pintype "input"))
      (node (ref "U24") (pin "19") (pinfunction "G_19") (pintype "input"))
      (node (ref "U25") (pin "1") (pinfunction "G_1") (pintype "input"))
      (node (ref "U25") (pin "19") (pinfunction "G_19") (pintype "input"))
      (node (ref "U29") (pin "15") (pinfunction "G_15") (pintype "input"))
      (node (ref "U5") (pin "15") (pinfunction "G_15") (pintype "input"))
      (node (ref "U8") (pin "1") (pinfunction "G_1") (pintype "input"))
      (node (ref "U9") (pin "5") (pinfunction "Q_5") (pintype "output"))
    )
    (net (code "151") (name "GND") (class "Default")
      (node (ref "C1") (pin "2") (pinfunction "2_2") (pintype "passive"))
      (node (ref "C10") (pin "2") (pinfunction "2_2") (pintype "passive"))
      (node (ref "C11") (pin "2") (pinfunction "2_2") (pintype "passive"))
      (node (ref "C12") (pin "2") (pinfunction "2_2") (pintype "passive"))
      (node (ref "C13") (pin "2") (pinfunction "2_2") (pintype "passive"))
      (node (ref "C14") (pin "2") (pinfunction "2_2") (pintype "passive"))
      (node (ref "C15") (pin "2") (pinfunction "2_2") (pintype "passive"))
      (node (ref "C16") (pin "2") (pinfunction "2_2") (pintype "passive"))
      (node (ref "C17") (pin "2") (pinfunction "2_2") (pintype "passive"))
      (node (ref "C18") (pin "2") (pinfunction "2_2") (pintype "passive"))
      (node (ref "C19") (pin "2") (pinfunction "2_2") (pintype "passive"))
      (node (ref "C2") (pin "2") (pinfunction "2_2") (pintype "passive"))
      (node (ref "C20") (pin "2") (pinfunction "2_2") (pintype "passive"))
      (node (ref "C21") (pin "2") (pinfunction "2_2") (pintype "passive"))
      (node (ref "C22") (pin "2") (pinfunction "2_2") (pintype "passive"))
      (node (ref "C23") (pin "2") (pinfunction "2_2") (pintype "passive"))
      (node (ref "C24") (pin "2") (pinfunction "2_2") (pintype "passive"))
      (node (ref "C25") (pin "2") (pinfunction "2_2") (pintype "passive"))
      (node (ref "C26") (pin "2") (pinfunction "2_2") (pintype "passive"))
      (node (ref "C27") (pin "2") (pinfunction "2_2") (pintype "passive"))
      (node (ref "C28") (pin "2") (pinfunction "2_2") (pintype "passive"))
      (node (ref "C29") (pin "2") (pinfunction "2_2") (pintype "passive"))
      (node (ref "C3") (pin "2") (pinfunction "2_2") (pintype "passive"))
      (node (ref "C30") (pin "2") (pinfunction "2_2") (pintype "passive"))
      (node (ref "C31") (pin "2") (pinfunction "2_2") (pintype "passive"))
      (node (ref "C32") (pin "2") (pinfunction "2_2") (pintype "passive"))
      (node (ref "C33") (pin "-") (pinfunction "-_-") (pintype "passive"))
      (node (ref "C4") (pin "2") (pinfunction "2_2") (pintype "passive"))
      (node (ref "C5") (pin "2") (pinfunction "2_2") (pintype "passive"))
      (node (ref "C6") (pin "2") (pinfunction "2_2") (pintype "passive"))
      (node (ref "C7") (pin "2") (pinfunction "2_2") (pintype "passive"))
      (node (ref "C8") (pin "2") (pinfunction "2_2") (pintype "passive"))
      (node (ref "C9") (pin "2") (pinfunction "2_2") (pintype "passive"))
      (node (ref "D1") (pin "K") (pinfunction "C_K") (pintype "passive"))
      (node (ref "PC0") (pin "3") (pinfunction "GND_3") (pintype "bidirectional"))
      (node (ref "PC0") (pin "4") (pinfunction "GND_4") (pintype "bidirectional"))
      (node (ref "PC0") (pin "62") (pinfunction "GND_62") (pintype "bidirectional"))
      (node (ref "R3") (pin "2") (pinfunction "2_2") (pintype "passive"))
      (node (ref "R4") (pin "2") (pinfunction "2_2") (pintype "passive"))
      (node (ref "U14") (pin "11") (pinfunction "A1_11") (pintype "input"))
      (node (ref "U14") (pin "13") (pinfunction "A2_13") (pintype "input"))
      (node (ref "U14") (pin "15") (pinfunction "A3_15") (pintype "input"))
      (node (ref "U14") (pin "17") (pinfunction "A4_17") (pintype "input"))
      (node (ref "U14") (pin "4") (pinfunction "A2_4") (pintype "input"))
      (node (ref "U14") (pin "6") (pinfunction "A3_6") (pintype "input"))
      (node (ref "U14") (pin "8") (pinfunction "A4_8") (pintype "input"))
      (node (ref "U16") (pin "2") (pinfunction "1D_2") (pintype "input"))
      (node (ref "U16") (pin "3") (pinfunction "2D_3") (pintype "input"))
      (node (ref "U16") (pin "8") (pinfunction "7D_8") (pintype "input"))
      (node (ref "U16") (pin "9") (pinfunction "8D_9") (pintype "input"))
      (node (ref "U23") (pin "5") (pinfunction "EI_5") (pintype "input"))
      (node (ref "U5") (pin "10") (pinfunction "3B_10") (pintype "input"))
      (node (ref "U5") (pin "13") (pinfunction "4B_13") (pintype "input"))
      (node (ref "U5") (pin "3") (pinfunction "1B_3") (pintype "input"))
      (node (ref "U5") (pin "6") (pinfunction "2B_6") (pintype "input"))
      (node (ref "U6") (pin "18") (pinfunction "Q7_18") (pintype "input"))
      (node (ref "U7") (pin "12") (pinfunction "Q4_12") (pintype "input"))
      (node (ref "U7") (pin "14") (pinfunction "Q5_14") (pintype "input"))
      (node (ref "U7") (pin "16") (pinfunction "Q6_16") (pintype "input"))
      (node (ref "U7") (pin "18") (pinfunction "Q7_18") (pintype "input"))
      (node (ref "U7") (pin "5") (pinfunction "Q1_5") (pintype "input"))
      (node (ref "U7") (pin "7") (pinfunction "Q2_7") (pintype "input"))
      (node (ref "U7") (pin "9") (pinfunction "Q3_9") (pintype "input"))
      (node (ref "U8") (pin "11") (pinfunction "A1_11") (pintype "input"))
      (node (ref "U8") (pin "19") (pinfunction "G_19") (pintype "input"))
      (node (ref "U8") (pin "8") (pinfunction "A4_8") (pintype "input"))
      (node (ref "U9") (pin "12") (pinfunction "D_12") (pintype "input"))
      (node (ref "Y1") (pin "4") (pinfunction "GND_4") (pintype "power_in"))
    )
    (net (code "152") (name "ID0") (class "Default")
      (node (ref "U13") (pin "2") (pinfunction "A1_2") (pintype "input"))
    )
    (net (code "153") (name "ID1") (class "Default")
      (node (ref "U13") (pin "17") (pinfunction "A4_17") (pintype "input"))
    )
    (net (code "154") (name "ID2") (class "Default")
      (node (ref "U13") (pin "4") (pinfunction "A2_4") (pintype "input"))
    )
    (net (code "155") (name "ID3") (class "Default")
      (node (ref "U13") (pin "15") (pinfunction "A3_15") (pintype "input"))
    )
    (net (code "156") (name "ID4") (class "Default")
      (node (ref "U13") (pin "6") (pinfunction "A3_6") (pintype "input"))
    )
    (net (code "157") (name "ID5") (class "Default")
      (node (ref "U13") (pin "13") (pinfunction "A2_13") (pintype "input"))
    )
    (net (code "158") (name "ID6") (class "Default")
      (node (ref "U13") (pin "8") (pinfunction "A4_8") (pintype "input"))
    )
    (net (code "159") (name "ID7") (class "Default")
      (node (ref "U13") (pin "11") (pinfunction "A1_11") (pintype "input"))
    )
    (net (code "160") (name "Net-(D1-PadA)") (class "Default")
      (node (ref "D1") (pin "A") (pinfunction "A_A") (pintype "passive"))
      (node (ref "R1") (pin "1") (pinfunction "1_1") (pintype "passive"))
    )
    (net (code "161") (name "Net-(Q1-B)") (class "Default")
      (node (ref "Q1") (pin "2") (pinfunction "B_2") (pintype "passive"))
      (node (ref "R2") (pin "2") (pinfunction "2_2") (pintype "passive"))
    )
    (net (code "162") (name "Net-(Q1-C)") (class "Default")
      (node (ref "Q1") (pin "3") (pinfunction "C_3") (pintype "passive"))
      (node (ref "R1") (pin "2") (pinfunction "2_2") (pintype "passive"))
    )
    (net (code "163") (name "Net-(U3A-I1)") (class "Default")
      (node (ref "U3") (pin "2") (pinfunction "I1_2") (pintype "input"))
      (node (ref "U4") (pin "6") (pinfunction "O_6") (pintype "output"))
    )
    (net (code "164") (name "Net-(U3B-O)") (class "Default")
      (node (ref "U3") (pin "6") (pinfunction "O_6") (pintype "output"))
      (node (ref "U4") (pin "5") (pinfunction "I_5") (pintype "input"))
    )
    (net (code "165") (name "Net-(U3C-I0)") (class "Default")
      (node (ref "JP3") (pin "1") (pinfunction "1_1") (pintype "passive"))
      (node (ref "R3") (pin "1") (pinfunction "1_1") (pintype "passive"))
      (node (ref "U3") (pin "9") (pinfunction "I0_9") (pintype "input"))
    )
    (net (code "166") (name "Net-(U3C-I1)") (class "Default")
      (node (ref "U3") (pin "10") (pinfunction "I1_10") (pintype "input"))
      (node (ref "U3") (pin "11") (pinfunction "O_11") (pintype "output"))
    )
    (net (code "167") (name "Net-(U3D-I0)") (class "Default")
      (node (ref "U3") (pin "12") (pinfunction "I0_12") (pintype "input"))
      (node (ref "U4") (pin "8") (pinfunction "O_8") (pintype "output"))
    )
    (net (code "168") (name "Net-(U3D-I1)") (class "Default")
      (node (ref "U3") (pin "13") (pinfunction "I1_13") (pintype "input"))
      (node (ref "U7") (pin "19") (pinfunction "P=Q_19") (pintype "output"))
    )
    (net (code "169") (name "Net-(U4A-O)") (class "Default")
      (node (ref "U4") (pin "2") (pinfunction "O_2") (pintype "output"))
      (node (ref "U7") (pin "1") (pinfunction "G_1") (pintype "input"))
    )
    (net (code "170") (name "Net-(U4B-I)") (class "Default")
      (node (ref "U4") (pin "12") (pinfunction "O_12") (pintype "output"))
      (node (ref "U4") (pin "3") (pinfunction "I_3") (pintype "input"))
    )
    (net (code "171") (name "Net-(U4B-O)") (class "Default")
      (node (ref "U4") (pin "4") (pinfunction "O_4") (pintype "output"))
      (node (ref "U9") (pin "3") (pinfunction "CLK_3") (pintype "input"))
    )
    (net (code "172") (name "Net-(U6A-G)") (class "Default")
      (node (ref "JP4") (pin "2") (pinfunction "2_2") (pintype "passive"))
      (node (ref "R4") (pin "1") (pinfunction "1_1") (pintype "passive"))
      (node (ref "U6") (pin "1") (pinfunction "G_1") (pintype "input"))
    )
    (net (code "173") (name "Net-(U10A-Q)") (class "Default")
      (node (ref "U10") (pin "5") (pinfunction "Q_5") (pintype "output"))
      (node (ref "U12") (pin "17") (pinfunction "A4_17") (pintype "input"))
      (node (ref "U29") (pin "2") (pinfunction "1A_2") (pintype "input"))
    )
    (net (code "174") (name "Net-(U10B-CLR)") (class "Default")
      (node (ref "U10") (pin "13") (pinfunction "CLR_13") (pintype "input"))
      (node (ref "U18") (pin "6") (pinfunction "O_6") (pintype "output"))
    )
    (net (code "175") (name "Net-(U11A-Q2)") (class "Default")
      (node (ref "U11") (pin "5") (pinfunction "Q2_5") (pintype "output"))
      (node (ref "U12") (pin "4") (pinfunction "A2_4") (pintype "input"))
      (node (ref "U5") (pin "11") (pinfunction "3A_11") (pintype "input"))
    )
    (net (code "176") (name "Net-(U11A-Q3)") (class "Default")
      (node (ref "U11") (pin "6") (pinfunction "Q3_6") (pintype "output"))
      (node (ref "U12") (pin "13") (pinfunction "A2_13") (pintype "input"))
      (node (ref "U5") (pin "14") (pinfunction "4A_14") (pintype "input"))
    )
    (net (code "177") (name "Net-(U11A-Q4)") (class "Default")
      (node (ref "U11") (pin "9") (pinfunction "Q4_9") (pintype "output"))
      (node (ref "U12") (pin "8") (pinfunction "A4_8") (pintype "input"))
      (node (ref "U4") (pin "1") (pinfunction "I_1") (pintype "input"))
    )
    (net (code "178") (name "Net-(U11A-Q5)") (class "Default")
      (node (ref "U11") (pin "12") (pinfunction "Q5_12") (pintype "output"))
      (node (ref "U12") (pin "11") (pinfunction "A1_11") (pintype "input"))
    )
    (net (code "179") (name "Net-(U11A-Q6)") (class "Default")
      (node (ref "U11") (pin "15") (pinfunction "Q6_15") (pintype "output"))
      (node (ref "U12") (pin "6") (pinfunction "A3_6") (pintype "input"))
    )
    (net (code "180") (name "Net-(U11A-Q7)") (class "Default")
      (node (ref "U11") (pin "16") (pinfunction "Q7_16") (pintype "output"))
      (node (ref "U12") (pin "15") (pinfunction "A3_15") (pintype "input"))
      (node (ref "U5") (pin "5") (pinfunction "2A_5") (pintype "input"))
    )
    (net (code "181") (name "Net-(U11A-Q8)") (class "Default")
      (node (ref "U11") (pin "19") (pinfunction "Q8_19") (pintype "output"))
      (node (ref "U12") (pin "2") (pinfunction "A1_2") (pintype "input"))
      (node (ref "U5") (pin "2") (pinfunction "1A_2") (pintype "input"))
    )
    (net (code "182") (name "Net-(U13A-G)") (class "Default")
      (node (ref "U1") (pin "7") (pinfunction "Y7_7") (pintype "output"))
      (node (ref "U13") (pin "1") (pinfunction "G_1") (pintype "input"))
      (node (ref "U13") (pin "19") (pinfunction "G_19") (pintype "input"))
    )
    (net (code "183") (name "Net-(U14A-G)") (class "Default")
      (node (ref "U14") (pin "1") (pinfunction "G_1") (pintype "input"))
      (node (ref "U14") (pin "19") (pinfunction "G_19") (pintype "input"))
      (node (ref "U22") (pin "7") (pinfunction "Y7_7") (pintype "output"))
    )
    (net (code "184") (name "Net-(U15A-B1)") (class "Default")
      (node (ref "U15") (pin "18") (pinfunction "B1_18") (pintype "bidirectional"))
      (node (ref "U20") (pin "33") (pinfunction "D0_33") (pintype "bidirectional"))
    )
    (net (code "185") (name "Net-(U15A-B2)") (class "Default")
      (node (ref "U15") (pin "17") (pinfunction "B2_17") (pintype "bidirectional"))
      (node (ref "U20") (pin "32") (pinfunction "D1_32") (pintype "bidirectional"))
    )
    (net (code "186") (name "Net-(U15A-B3)") (class "Default")
      (node (ref "U15") (pin "16") (pinfunction "B3_16") (pintype "bidirectional"))
      (node (ref "U20") (pin "31") (pinfunction "D2_31") (pintype "bidirectional"))
    )
    (net (code "187") (name "Net-(U15A-B4)") (class "Default")
      (node (ref "U15") (pin "15") (pinfunction "B4_15") (pintype "bidirectional"))
      (node (ref "U20") (pin "30") (pinfunction "D3_30") (pintype "bidirectional"))
    )
    (net (code "188") (name "Net-(U15A-B5)") (class "Default")
      (node (ref "U15") (pin "14") (pinfunction "B5_14") (pintype "bidirectional"))
      (node (ref "U20") (pin "29") (pinfunction "D4_29") (pintype "bidirectional"))
    )
    (net (code "189") (name "Net-(U15A-B6)") (class "Default")
      (node (ref "U15") (pin "13") (pinfunction "B6_13") (pintype "bidirectional"))
      (node (ref "U20") (pin "28") (pinfunction "D5_28") (pintype "bidirectional"))
    )
    (net (code "190") (name "Net-(U15A-B7)") (class "Default")
      (node (ref "U15") (pin "12") (pinfunction "B7_12") (pintype "bidirectional"))
      (node (ref "U20") (pin "27") (pinfunction "D6_27") (pintype "bidirectional"))
    )
    (net (code "191") (name "Net-(U15A-B8)") (class "Default")
      (node (ref "U15") (pin "11") (pinfunction "B8_11") (pintype "bidirectional"))
      (node (ref "U20") (pin "26") (pinfunction "D7_26") (pintype "bidirectional"))
    )
    (net (code "192") (name "Net-(U15A-DIR)") (class "Default")
      (node (ref "U15") (pin "1") (pinfunction "DIR_1") (pintype "input"))
      (node (ref "U17") (pin "1") (pinfunction "I0_1") (pintype "input"))
      (node (ref "U19") (pin "3") (pinfunction "I_3") (pintype "input"))
      (node (ref "U20") (pin "34") (pinfunction "R~{WB}_34") (pintype "output"))
    )
    (net (code "193") (name "Net-(U16A-3D)") (class "Default")
      (node (ref "U16") (pin "4") (pinfunction "3D_4") (pintype "input"))
      (node (ref "U23") (pin "9") (pinfunction "A0_9") (pintype "output"))
    )
    (net (code "194") (name "Net-(U16A-4D)") (class "Default")
      (node (ref "U16") (pin "5") (pinfunction "4D_5") (pintype "input"))
      (node (ref "U23") (pin "7") (pinfunction "A1_7") (pintype "output"))
    )
    (net (code "195") (name "Net-(U16A-5D)") (class "Default")
      (node (ref "U16") (pin "6") (pinfunction "5D_6") (pintype "input"))
      (node (ref "U23") (pin "6") (pinfunction "A2_6") (pintype "output"))
    )
    (net (code "196") (name "Net-(U16A-6D)") (class "Default")
      (node (ref "U16") (pin "7") (pinfunction "6D_7") (pintype "input"))
      (node (ref "U19") (pin "10") (pinfunction "O_10") (pintype "output"))
    )
    (net (code "197") (name "Net-(U16A-OC)") (class "Default")
      (node (ref "U16") (pin "1") (pinfunction "OC_1") (pintype "input"))
      (node (ref "U22") (pin "9") (pinfunction "Y6_9") (pintype "output"))
    )
    (net (code "198") (name "Net-(U17A-I1)") (class "Default")
      (node (ref "JP1") (pin "2") (pinfunction "2_2") (pintype "passive"))
      (node (ref "U17") (pin "2") (pinfunction "I1_2") (pintype "input"))
      (node (ref "U17") (pin "4") (pinfunction "I0_4") (pintype "input"))
      (node (ref "U20") (pin "37") (pinfunction "PHI2_37") (pintype "input"))
      (node (ref "U8") (pin "17") (pinfunction "A4_17") (pintype "input"))
    )
    (net (code "199") (name "Net-(U17B-I1)") (class "Default")
      (node (ref "U17") (pin "5") (pinfunction "I1_5") (pintype "input"))
      (node (ref "U19") (pin "4") (pinfunction "O_4") (pintype "output"))
    )
    (net (code "200") (name "Net-(U17C-I1)") (class "Default")
      (node (ref "U17") (pin "10") (pinfunction "I1_10") (pintype "input"))
      (node (ref "U19") (pin "12") (pinfunction "O_12") (pintype "output"))
    )
    (net (code "201") (name "Net-(U17D-I0)") (class "Default")
      (node (ref "U17") (pin "12") (pinfunction "I0_12") (pintype "input"))
      (node (ref "U18") (pin "11") (pinfunction "O_11") (pintype "output"))
    )
    (net (code "202") (name "Net-(U17D-I1)") (class "Default")
      (node (ref "U17") (pin "13") (pinfunction "I1_13") (pintype "input"))
      (node (ref "U19") (pin "6") (pinfunction "O_6") (pintype "output"))
    )
    (net (code "203") (name "Net-(U18A-I0)") (class "Default")
      (node (ref "U18") (pin "1") (pinfunction "I0_1") (pintype "input"))
      (node (ref "U4") (pin "10") (pinfunction "O_10") (pintype "output"))
    )
    (net (code "204") (name "Net-(U18A-O)") (class "Default")
      (node (ref "U18") (pin "3") (pinfunction "O_3") (pintype "output"))
      (node (ref "U9") (pin "2") (pinfunction "D_2") (pintype "input"))
    )
    (net (code "205") (name "Net-(U18C-O)") (class "Default")
      (node (ref "U18") (pin "8") (pinfunction "O_8") (pintype "output"))
      (node (ref "U20") (pin "4") (pinfunction "~{IRQB}_4") (pintype "input"))
    )
    (net (code "206") (name "Net-(U19D-I)") (class "Default")
      (node (ref "U19") (pin "9") (pinfunction "I_9") (pintype "input"))
      (node (ref "U20") (pin "7") (pinfunction "SYNC_7") (pintype "output"))
    )
    (net (code "207") (name "Net-(U19D-O)") (class "Default")
      (node (ref "U19") (pin "8") (pinfunction "O_8") (pintype "output"))
      (node (ref "U8") (pin "6") (pinfunction "A3_6") (pintype "input"))
    )
    (net (code "208") (name "Net-(U19E-I)") (class "Default")
      (node (ref "U19") (pin "11") (pinfunction "I_11") (pintype "input"))
      (node (ref "U23") (pin "15") (pinfunction "EO_15") (pintype "output"))
    )
    (net (code "209") (name "Net-(U20A-~{NMIB})") (class "Default")
      (node (ref "JP5") (pin "2") (pinfunction "2_2") (pintype "passive"))
      (node (ref "R6") (pin "1") (pinfunction "1_1") (pintype "passive"))
      (node (ref "U20") (pin "6") (pinfunction "~{NMIB}_6") (pintype "input"))
    )
    (net (code "210") (name "Net-(U21A-A1)") (class "Default")
      (node (ref "U21") (pin "2") (pinfunction "A1_2") (pintype "input"))
      (node (ref "U26") (pin "19") (pinfunction "Q8_19") (pintype "output"))
      (node (ref "U27") (pin "1") (pinfunction "I0_1") (pintype "input"))
    )
    (net (code "211") (name "Net-(U21A-A2)") (class "Default")
      (node (ref "U21") (pin "4") (pinfunction "A2_4") (pintype "input"))
      (node (ref "U26") (pin "16") (pinfunction "Q7_16") (pintype "output"))
      (node (ref "U27") (pin "4") (pinfunction "I0_4") (pintype "input"))
    )
    (net (code "212") (name "Net-(U21A-A3)") (class "Default")
      (node (ref "U21") (pin "6") (pinfunction "A3_6") (pintype "input"))
      (node (ref "U26") (pin "15") (pinfunction "Q6_15") (pintype "output"))
      (node (ref "U27") (pin "12") (pinfunction "I0_12") (pintype "input"))
    )
    (net (code "213") (name "Net-(U21A-A4)") (class "Default")
      (node (ref "U21") (pin "8") (pinfunction "A4_8") (pintype "input"))
      (node (ref "U26") (pin "12") (pinfunction "Q5_12") (pintype "output"))
      (node (ref "U27") (pin "9") (pinfunction "I0_9") (pintype "input"))
    )
    (net (code "214") (name "Net-(U21B-A1)") (class "Default")
      (node (ref "U21") (pin "11") (pinfunction "A1_11") (pintype "input"))
      (node (ref "U26") (pin "9") (pinfunction "Q4_9") (pintype "output"))
      (node (ref "U28") (pin "4") (pinfunction "I0_4") (pintype "input"))
    )
    (net (code "215") (name "Net-(U21B-A2)") (class "Default")
      (node (ref "U21") (pin "13") (pinfunction "A2_13") (pintype "input"))
      (node (ref "U26") (pin "6") (pinfunction "Q3_6") (pintype "output"))
      (node (ref "U28") (pin "1") (pinfunction "I0_1") (pintype "input"))
    )
    (net (code "216") (name "Net-(U21B-A3)") (class "Default")
      (node (ref "U21") (pin "15") (pinfunction "A3_15") (pintype "input"))
      (node (ref "U26") (pin "5") (pinfunction "Q2_5") (pintype "output"))
      (node (ref "U28") (pin "12") (pinfunction "I0_12") (pintype "input"))
    )
    (net (code "217") (name "Net-(U21B-A4)") (class "Default")
      (node (ref "U21") (pin "17") (pinfunction "A4_17") (pintype "input"))
      (node (ref "U26") (pin "2") (pinfunction "Q1_2") (pintype "output"))
      (node (ref "U28") (pin "9") (pinfunction "I0_9") (pintype "input"))
    )
    (net (code "218") (name "Net-(U23A-0)") (class "Default")
      (node (ref "U23") (pin "10") (pinfunction "0_10") (pintype "input"))
      (node (ref "U28") (pin "8") (pinfunction "O_8") (pintype "output"))
    )
    (net (code "219") (name "Net-(U23A-1)") (class "Default")
      (node (ref "U23") (pin "11") (pinfunction "1_11") (pintype "input"))
      (node (ref "U28") (pin "11") (pinfunction "O_11") (pintype "output"))
    )
    (net (code "220") (name "Net-(U23A-2)") (class "Default")
      (node (ref "U23") (pin "12") (pinfunction "2_12") (pintype "input"))
      (node (ref "U28") (pin "3") (pinfunction "O_3") (pintype "output"))
    )
    (net (code "221") (name "Net-(U23A-3)") (class "Default")
      (node (ref "U23") (pin "13") (pinfunction "3_13") (pintype "input"))
      (node (ref "U28") (pin "6") (pinfunction "O_6") (pintype "output"))
    )
    (net (code "222") (name "Net-(U23A-4)") (class "Default")
      (node (ref "U23") (pin "1") (pinfunction "4_1") (pintype "input"))
      (node (ref "U27") (pin "8") (pinfunction "O_8") (pintype "output"))
    )
    (net (code "223") (name "Net-(U23A-5)") (class "Default")
      (node (ref "U23") (pin "2") (pinfunction "5_2") (pintype "input"))
      (node (ref "U27") (pin "11") (pinfunction "O_11") (pintype "output"))
    )
    (net (code "224") (name "Net-(U23A-6)") (class "Default")
      (node (ref "U23") (pin "3") (pinfunction "6_3") (pintype "input"))
      (node (ref "U27") (pin "6") (pinfunction "O_6") (pintype "output"))
    )
    (net (code "225") (name "Net-(U23A-7)") (class "Default")
      (node (ref "U23") (pin "4") (pinfunction "7_4") (pintype "input"))
      (node (ref "U27") (pin "3") (pinfunction "O_3") (pintype "output"))
    )
    (net (code "226") (name "Net-(U29A-~{A}{slash}B)") (class "Default")
      (node (ref "U29") (pin "1") (pinfunction "~{A}/B_1") (pintype "input"))
      (node (ref "U3") (pin "8") (pinfunction "O_8") (pintype "output"))
      (node (ref "U5") (pin "1") (pinfunction "~{A}/B_1") (pintype "input"))
    )
    (net (code "227") (name "Net-(U30A-CLK)") (class "Default")
      (node (ref "JP1") (pin "3") (pinfunction "3_3") (pintype "passive"))
      (node (ref "U30") (pin "11") (pinfunction "CLK_11") (pintype "input"))
      (node (ref "U30") (pin "3") (pinfunction "CLK_3") (pintype "input"))
      (node (ref "Y1") (pin "5") (pinfunction "FO_5") (pintype "output"))
    )
    (net (code "228") (name "Net-(U30A-D)") (class "Default")
      (node (ref "U3") (pin "3") (pinfunction "O_3") (pintype "output"))
      (node (ref "U30") (pin "2") (pinfunction "D_2") (pintype "input"))
    )
    (net (code "229") (name "Net-(U30A-Q)") (class "Default")
      (node (ref "JP1") (pin "1") (pinfunction "1_1") (pintype "passive"))
      (node (ref "JP2") (pin "3") (pinfunction "3_3") (pintype "passive"))
      (node (ref "U3") (pin "1") (pinfunction "I0_1") (pintype "input"))
      (node (ref "U30") (pin "5") (pinfunction "Q_5") (pintype "output"))
    )
    (net (code "230") (name "Net-(U30B-D)") (class "Default")
      (node (ref "JP2") (pin "2") (pinfunction "2_2") (pintype "passive"))
      (node (ref "U30") (pin "12") (pinfunction "D_12") (pintype "input"))
    )
    (net (code "231") (name "Net-(U30B-Q)") (class "Default")
      (node (ref "U3") (pin "5") (pinfunction "I1_5") (pintype "input"))
      (node (ref "U30") (pin "9") (pinfunction "Q_9") (pintype "output"))
    )
    (net (code "232") (name "Net-(U31A-O)") (class "Default")
      (node (ref "U31") (pin "11") (pinfunction "I_11") (pintype "input"))
      (node (ref "U31") (pin "12") (pinfunction "O_12") (pintype "output"))
    )
    (net (code "233") (name "Net-(U31B-O)") (class "Default")
      (node (ref "U3") (pin "4") (pinfunction "I0_4") (pintype "input"))
      (node (ref "U31") (pin "10") (pinfunction "O_10") (pintype "output"))
    )
    (net (code "234") (name "Net-(U31D-O)") (class "Default")
      (node (ref "U31") (pin "2") (pinfunction "O_2") (pintype "output"))
      (node (ref "U31") (pin "3") (pinfunction "I_3") (pintype "input"))
    )
    (net (code "235") (name "Net-(Y1-OE)") (class "Default")
      (node (ref "R5") (pin "1") (pinfunction "1_1") (pintype "passive"))
      (node (ref "Y1") (pin "1") (pinfunction "OE_1") (pintype "input"))
    )
    (net (code "236") (name "PH1") (class "Default")
      (node (ref "U16") (pin "11") (pinfunction "CLK_11") (pintype "input"))
      (node (ref "U20") (pin "3") (pinfunction "PHI1O_3") (pintype "output"))
      (node (ref "U9") (pin "11") (pinfunction "CLK_11") (pintype "input"))
    )
    (net (code "237") (name "PH2") (class "Default")
      (node (ref "U20") (pin "39") (pinfunction "PHI2O_39") (pintype "output"))
      (node (ref "U4") (pin "13") (pinfunction "I_13") (pintype "input"))
    )
    (net (code "238") (name "RDY") (class "Default")
      (node (ref "R7") (pin "1") (pinfunction "1_1") (pintype "passive"))
      (node (ref "U19") (pin "13") (pinfunction "I_13") (pintype "input"))
      (node (ref "U20") (pin "2") (pinfunction "RDY_2") (pintype "bidirectional"))
    )
    (net (code "239") (name "VCC") (class "Default")
      (node (ref "C1") (pin "1") (pinfunction "1_1") (pintype "passive"))
      (node (ref "C10") (pin "1") (pinfunction "1_1") (pintype "passive"))
      (node (ref "C11") (pin "1") (pinfunction "1_1") (pintype "passive"))
      (node (ref "C12") (pin "1") (pinfunction "1_1") (pintype "passive"))
      (node (ref "C13") (pin "1") (pinfunction "1_1") (pintype "passive"))
      (node (ref "C14") (pin "1") (pinfunction "1_1") (pintype "passive"))
      (node (ref "C15") (pin "1") (pinfunction "1_1") (pintype "passive"))
      (node (ref "C16") (pin "1") (pinfunction "1_1") (pintype "passive"))
      (node (ref "C17") (pin "1") (pinfunction "1_1") (pintype "passive"))
      (node (ref "C18") (pin "1") (pinfunction "1_1") (pintype "passive"))
      (node (ref "C19") (pin "1") (pinfunction "1_1") (pintype "passive"))
      (node (ref "C2") (pin "1") (pinfunction "1_1") (pintype "passive"))
      (node (ref "C20") (pin "1") (pinfunction "1_1") (pintype "passive"))
      (node (ref "C21") (pin "1") (pinfunction "1_1") (pintype "passive"))
      (node (ref "C22") (pin "1") (pinfunction "1_1") (pintype "passive"))
      (node (ref "C23") (pin "1") (pinfunction "1_1") (pintype "passive"))
      (node (ref "C24") (pin "1") (pinfunction "1_1") (pintype "passive"))
      (node (ref "C25") (pin "1") (pinfunction "1_1") (pintype "passive"))
      (node (ref "C26") (pin "1") (pinfunction "1_1") (pintype "passive"))
      (node (ref "C27") (pin "1") (pinfunction "1_1") (pintype "passive"))
      (node (ref "C28") (pin "1") (pinfunction "1_1") (pintype "passive"))
      (node (ref "C29") (pin "1") (pinfunction "1_1") (pintype "passive"))
      (node (ref "C3") (pin "1") (pinfunction "1_1") (pintype "passive"))
      (node (ref "C30") (pin "1") (pinfunction "1_1") (pintype "passive"))
      (node (ref "C31") (pin "1") (pinfunction "1_1") (pintype "passive"))
      (node (ref "C32") (pin "1") (pinfunction "1_1") (pintype "passive"))
      (node (ref "C33") (pin "+") (pinfunction "+_+") (pintype "passive"))
      (node (ref "C4") (pin "1") (pinfunction "1_1") (pintype "passive"))
      (node (ref "C5") (pin "1") (pinfunction "1_1") (pintype "passive"))
      (node (ref "C6") (pin "1") (pinfunction "1_1") (pintype "passive"))
      (node (ref "C7") (pin "1") (pinfunction "1_1") (pintype "passive"))
      (node (ref "C8") (pin "1") (pinfunction "1_1") (pintype "passive"))
      (node (ref "C9") (pin "1") (pinfunction "1_1") (pintype "passive"))
      (node (ref "JP2") (pin "1") (pinfunction "1_1") (pintype "passive"))
      (node (ref "JP4") (pin "1") (pinfunction "1_1") (pintype "passive"))
      (node (ref "PC0") (pin "5") (pinfunction "+5V_5") (pintype "bidirectional"))
      (node (ref "PC0") (pin "6") (pinfunction "+5V_6") (pintype "bidirectional"))
      (node (ref "Q1") (pin "1") (pinfunction "E_1") (pintype "passive"))
      (node (ref "R5") (pin "2") (pinfunction "2_2") (pintype "passive"))
      (node (ref "R6") (pin "2") (pinfunction "2_2") (pintype "passive"))
      (node (ref "U10") (pin "1") (pinfunction "CLR_1") (pintype "input"))
      (node (ref "U10") (pin "11") (pinfunction "CLK_11") (pintype "input"))
      (node (ref "U10") (pin "12") (pinfunction "D_12") (pintype "input"))
      (node (ref "U11") (pin "3") (pinfunction "D1_3") (pintype "input"))
      (node (ref "U14") (pin "2") (pinfunction "A1_2") (pintype "input"))
      (node (ref "U19") (pin "1") (pinfunction "I_1") (pintype "input"))
      (node (ref "U2") (pin "6") (pinfunction "G1_6") (pintype "input"))
      (node (ref "U20") (pin "36") (pinfunction "BE_36") (pintype "input"))
      (node (ref "U20") (pin "38") (pinfunction "~{SOB}_38") (pintype "input"))
      (node (ref "U22") (pin "6") (pinfunction "G1_6") (pintype "input"))
      (node (ref "U29") (pin "10") (pinfunction "3B_10") (pintype "input"))
      (node (ref "U29") (pin "11") (pinfunction "3A_11") (pintype "input"))
      (node (ref "U29") (pin "13") (pinfunction "4B_13") (pintype "input"))
      (node (ref "U29") (pin "14") (pinfunction "4A_14") (pintype "input"))
      (node (ref "U29") (pin "5") (pinfunction "2A_5") (pintype "input"))
      (node (ref "U29") (pin "6") (pinfunction "2B_6") (pintype "input"))
      (node (ref "U30") (pin "1") (pinfunction "CLR_1") (pintype "input"))
      (node (ref "U30") (pin "10") (pinfunction "PRE_10") (pintype "input"))
      (node (ref "U30") (pin "13") (pinfunction "CLR_13") (pintype "input"))
      (node (ref "U30") (pin "4") (pinfunction "PRE_4") (pintype "input"))
      (node (ref "U31") (pin "5") (pinfunction "I_5") (pintype "input"))
      (node (ref "U31") (pin "9") (pinfunction "I_9") (pintype "input"))
      (node (ref "U6") (pin "12") (pinfunction "Q4_12") (pintype "input"))
      (node (ref "U6") (pin "14") (pinfunction "Q5_14") (pintype "input"))
      (node (ref "U6") (pin "16") (pinfunction "Q6_16") (pintype "input"))
      (node (ref "U6") (pin "2") (pinfunction "P0_2") (pintype "input"))
      (node (ref "U6") (pin "3") (pinfunction "Q0_3") (pintype "input"))
      (node (ref "U6") (pin "4") (pinfunction "P1_4") (pintype "input"))
      (node (ref "U6") (pin "5") (pinfunction "Q1_5") (pintype "input"))
      (node (ref "U6") (pin "6") (pinfunction "P2_6") (pintype "input"))
      (node (ref "U6") (pin "7") (pinfunction "Q2_7") (pintype "input"))
      (node (ref "U6") (pin "8") (pinfunction "P3_8") (pintype "input"))
      (node (ref "U6") (pin "9") (pinfunction "Q3_9") (pintype "input"))
      (node (ref "U7") (pin "2") (pinfunction "P0_2") (pintype "input"))
      (node (ref "U7") (pin "3") (pinfunction "Q0_3") (pintype "input"))
      (node (ref "U9") (pin "4") (pinfunction "PRE_4") (pintype "input"))
      (node (ref "Y1") (pin "8") (pinfunction "VCC_8") (pintype "power_in"))
    )
    (net (code "240") (name "unconnected-(PC0-+3.3V-Pad2)") (class "Default")
      (node (ref "PC0") (pin "2") (pinfunction "+3.3V_2") (pintype "bidirectional"))
    )
    (net (code "241") (name "unconnected-(PC0-+5VSB-Pad8)") (class "Default")
      (node (ref "PC0") (pin "8") (pinfunction "+5VSB_8") (pintype "bidirectional"))
    )
    (net (code "242") (name "unconnected-(PC0-+12V-Pad1)") (class "Default")
      (node (ref "PC0") (pin "1") (pinfunction "+12V_1") (pintype "bidirectional"))
    )
    (net (code "243") (name "unconnected-(PC0--12V-Pad7)") (class "Default")
      (node (ref "PC0") (pin "7") (pinfunction "-12V_7") (pintype "bidirectional"))
    )
    (net (code "244") (name "unconnected-(PC0-~{BUSRQ}-Pad10)") (class "Default")
      (node (ref "PC0") (pin "10") (pinfunction "~{BUSRQ}_10") (pintype "bidirectional"))
    )
    (net (code "245") (name "unconnected-(PC0-~{CINH}-Pad13)") (class "Default")
      (node (ref "PC0") (pin "13") (pinfunction "~{CINH}_13") (pintype "bidirectional"))
    )
    (net (code "246") (name "unconnected-(U1A-Y0-Pad15)") (class "Default")
      (node (ref "U1") (pin "15") (pinfunction "Y0_15") (pintype "output"))
    )
    (net (code "247") (name "unconnected-(U1A-Y1-Pad14)") (class "Default")
      (node (ref "U1") (pin "14") (pinfunction "Y1_14") (pintype "output"))
    )
    (net (code "248") (name "unconnected-(U1A-Y2-Pad13)") (class "Default")
      (node (ref "U1") (pin "13") (pinfunction "Y2_13") (pintype "output"))
    )
    (net (code "249") (name "unconnected-(U1A-Y3-Pad12)") (class "Default")
      (node (ref "U1") (pin "12") (pinfunction "Y3_12") (pintype "output"))
    )
    (net (code "250") (name "unconnected-(U1A-Y4-Pad11)") (class "Default")
      (node (ref "U1") (pin "11") (pinfunction "Y4_11") (pintype "output"))
    )
    (net (code "251") (name "unconnected-(U1A-Y5-Pad10)") (class "Default")
      (node (ref "U1") (pin "10") (pinfunction "Y5_10") (pintype "output"))
    )
    (net (code "252") (name "unconnected-(U1A-Y6-Pad9)") (class "Default")
      (node (ref "U1") (pin "9") (pinfunction "Y6_9") (pintype "output"))
    )
    (net (code "253") (name "unconnected-(U2A-Y0-Pad15)") (class "Default")
      (node (ref "U2") (pin "15") (pinfunction "Y0_15") (pintype "output"))
    )
    (net (code "254") (name "unconnected-(U2A-Y1-Pad14)") (class "Default")
      (node (ref "U2") (pin "14") (pinfunction "Y1_14") (pintype "output"))
    )
    (net (code "255") (name "unconnected-(U2A-Y6-Pad9)") (class "Default")
      (node (ref "U2") (pin "9") (pinfunction "Y6_9") (pintype "output"))
    )
    (net (code "256") (name "unconnected-(U2A-Y7-Pad7)") (class "Default")
      (node (ref "U2") (pin "7") (pinfunction "Y7_7") (pintype "output"))
    )
    (net (code "257") (name "unconnected-(U8A-Y4-Pad12)") (class "Default")
      (node (ref "U8") (pin "12") (pinfunction "Y4_12") (pintype "tri_state"))
    )
    (net (code "258") (name "unconnected-(U8B-Y1-Pad9)") (class "Default")
      (node (ref "U8") (pin "9") (pinfunction "Y1_9") (pintype "tri_state"))
    )
    (net (code "259") (name "unconnected-(U9B-Q-Pad9)") (class "Default")
      (node (ref "U9") (pin "9") (pinfunction "Q_9") (pintype "output"))
    )
    (net (code "260") (name "unconnected-(U10A-~{Q}-Pad6)") (class "Default")
      (node (ref "U10") (pin "6") (pinfunction "~{Q}_6") (pintype "output"))
    )
    (net (code "261") (name "unconnected-(U10B-Q-Pad9)") (class "Default")
      (node (ref "U10") (pin "9") (pinfunction "Q_9") (pintype "output"))
    )
    (net (code "262") (name "unconnected-(U11A-Q1-Pad2)") (class "Default")
      (node (ref "U11") (pin "2") (pinfunction "Q1_2") (pintype "output"))
    )
    (net (code "263") (name "unconnected-(U19A-O-Pad2)") (class "Default")
      (node (ref "U19") (pin "2") (pinfunction "O_2") (pintype "output"))
    )
    (net (code "264") (name "unconnected-(U22A-Y0-Pad15)") (class "Default")
      (node (ref "U22") (pin "15") (pinfunction "Y0_15") (pintype "output"))
    )
    (net (code "265") (name "unconnected-(U22A-Y1-Pad14)") (class "Default")
      (node (ref "U22") (pin "14") (pinfunction "Y1_14") (pintype "output"))
    )
    (net (code "266") (name "unconnected-(U22A-Y2-Pad13)") (class "Default")
      (node (ref "U22") (pin "13") (pinfunction "Y2_13") (pintype "output"))
    )
    (net (code "267") (name "unconnected-(U22A-Y3-Pad12)") (class "Default")
      (node (ref "U22") (pin "12") (pinfunction "Y3_12") (pintype "output"))
    )
    (net (code "268") (name "unconnected-(U22A-Y4-Pad11)") (class "Default")
      (node (ref "U22") (pin "11") (pinfunction "Y4_11") (pintype "output"))
    )
    (net (code "269") (name "unconnected-(U22A-Y5-Pad10)") (class "Default")
      (node (ref "U22") (pin "10") (pinfunction "Y5_10") (pintype "output"))
    )
    (net (code "270") (name "unconnected-(U29A-2Y-Pad7)") (class "Default")
      (node (ref "U29") (pin "7") (pinfunction "2Y_7") (pintype "tri_state"))
    )
    (net (code "271") (name "unconnected-(U29A-3Y-Pad9)") (class "Default")
      (node (ref "U29") (pin "9") (pinfunction "3Y_9") (pintype "tri_state"))
    )
    (net (code "272") (name "unconnected-(U29A-4Y-Pad12)") (class "Default")
      (node (ref "U29") (pin "12") (pinfunction "4Y_12") (pintype "tri_state"))
    )
    (net (code "273") (name "unconnected-(U30A-~{Q}-Pad6)") (class "Default")
      (node (ref "U30") (pin "6") (pinfunction "~{Q}_6") (pintype "output"))
    )
    (net (code "274") (name "unconnected-(U30B-~{Q}-Pad8)") (class "Default")
      (node (ref "U30") (pin "8") (pinfunction "~{Q}_8") (pintype "output"))
    )
    (net (code "275") (name "unconnected-(U31C-O-Pad8)") (class "Default")
      (node (ref "U31") (pin "8") (pinfunction "O_8") (pintype "output"))
    )
    (net (code "276") (name "unconnected-(U31F-O-Pad6)") (class "Default")
      (node (ref "U31") (pin "6") (pinfunction "O_6") (pintype "output"))
    )
    (net (code "277") (name "~{BBUSACK}") (class "Default")
      (node (ref "PC0") (pin "20") (pinfunction "~{BUSACK}_20") (pintype "bidirectional"))
      (node (ref "U8") (pin "7") (pinfunction "Y2_7") (pintype "tri_state"))
    )
    (net (code "278") (name "~{BCBR}") (class "Default")
      (node (ref "PC0") (pin "12") (pinfunction "~{CBR}_12") (pintype "bidirectional"))
      (node (ref "U4") (pin "11") (pinfunction "I_11") (pintype "input"))
    )
    (net (code "279") (name "~{BCSX}") (class "Default")
      (node (ref "PC0") (pin "9") (pinfunction "~{CSX}_9") (pintype "bidirectional"))
      (node (ref "U1") (pin "4") (pinfunction "G2A_4") (pintype "input"))
      (node (ref "U2") (pin "5") (pinfunction "G2B_5") (pintype "input"))
    )
    (net (code "280") (name "~{BFETCH}") (class "Default")
      (node (ref "PC0") (pin "19") (pinfunction "~{FETCH}_19") (pintype "bidirectional"))
      (node (ref "U8") (pin "14") (pinfunction "Y3_14") (pintype "tri_state"))
    )
    (net (code "281") (name "~{BHALT}") (class "Default")
      (node (ref "PC0") (pin "17") (pinfunction "~{HALT}_17") (pintype "bidirectional"))
      (node (ref "U8") (pin "5") (pinfunction "Y3_5") (pintype "tri_state"))
    )
    (net (code "282") (name "~{BINH}") (class "Default")
      (node (ref "PC0") (pin "11") (pinfunction "~{INH}_11") (pintype "bidirectional"))
      (node (ref "U17") (pin "11") (pinfunction "O_11") (pintype "output"))
    )
    (net (code "283") (name "~{BINT}") (class "Default")
      (node (ref "PC0") (pin "51") (pinfunction "~{INT}_51") (pintype "bidirectional"))
      (node (ref "U18") (pin "10") (pinfunction "I1_10") (pintype "input"))
    )
    (net (code "284") (name "~{BIOSEL}") (class "Default")
      (node (ref "PC0") (pin "16") (pinfunction "~{IOSEL}_16") (pintype "bidirectional"))
      (node (ref "U25") (pin "18") (pinfunction "Y1_18") (pintype "tri_state"))
    )
    (net (code "285") (name "~{BIRQ0}") (class "Default")
      (node (ref "PC0") (pin "53") (pinfunction "~{IRQ0}_53") (pintype "bidirectional"))
      (node (ref "U27") (pin "2") (pinfunction "I1_2") (pintype "input"))
    )
    (net (code "286") (name "~{BIRQ1}") (class "Default")
      (node (ref "PC0") (pin "54") (pinfunction "~{IRQ1}_54") (pintype "bidirectional"))
      (node (ref "U27") (pin "5") (pinfunction "I1_5") (pintype "input"))
    )
    (net (code "287") (name "~{BIRQ2}") (class "Default")
      (node (ref "PC0") (pin "55") (pinfunction "~{IRQ2}_55") (pintype "bidirectional"))
      (node (ref "U27") (pin "13") (pinfunction "I1_13") (pintype "input"))
    )
    (net (code "288") (name "~{BIRQ3}") (class "Default")
      (node (ref "PC0") (pin "56") (pinfunction "~{IRQ3}_56") (pintype "bidirectional"))
      (node (ref "U27") (pin "10") (pinfunction "I1_10") (pintype "input"))
    )
    (net (code "289") (name "~{BIRQ4}") (class "Default")
      (node (ref "PC0") (pin "57") (pinfunction "~{IRQ4}_57") (pintype "bidirectional"))
      (node (ref "U28") (pin "5") (pinfunction "I1_5") (pintype "input"))
    )
    (net (code "290") (name "~{BIRQ5}") (class "Default")
      (node (ref "PC0") (pin "58") (pinfunction "~{IRQ5}_58") (pintype "bidirectional"))
      (node (ref "U28") (pin "2") (pinfunction "I1_2") (pintype "input"))
    )
    (net (code "291") (name "~{BIRQ6}") (class "Default")
      (node (ref "PC0") (pin "59") (pinfunction "~{IRQ6}_59") (pintype "bidirectional"))
      (node (ref "U28") (pin "13") (pinfunction "I1_13") (pintype "input"))
    )
    (net (code "292") (name "~{BIRQ7}") (class "Default")
      (node (ref "PC0") (pin "60") (pinfunction "~{IRQ7}_60") (pintype "bidirectional"))
      (node (ref "U28") (pin "10") (pinfunction "I1_10") (pintype "input"))
    )
    (net (code "293") (name "~{BIRQX}") (class "Default")
      (node (ref "PC0") (pin "52") (pinfunction "~{IRQX}_52") (pintype "bidirectional"))
      (node (ref "U10") (pin "8") (pinfunction "~{Q}_8") (pintype "output"))
    )
    (net (code "294") (name "~{BNMI}") (class "Default")
      (node (ref "JP5") (pin "1") (pinfunction "1_1") (pintype "passive"))
      (node (ref "PC0") (pin "61") (pinfunction "~{NMI}_61") (pintype "bidirectional"))
    )
    (net (code "295") (name "~{BRD}") (class "Default")
      (node (ref "PC0") (pin "21") (pinfunction "~{RD}_21") (pintype "bidirectional"))
      (node (ref "U1") (pin "5") (pinfunction "G2B_5") (pintype "input"))
      (node (ref "U2") (pin "2") (pinfunction "B_2") (pintype "input"))
      (node (ref "U8") (pin "18") (pinfunction "Y1_18") (pintype "tri_state"))
    )
    (net (code "296") (name "~{BRST}") (class "Default")
      (node (ref "PC0") (pin "14") (pinfunction "~{RST}_14") (pintype "bidirectional"))
      (node (ref "U31") (pin "1") (pinfunction "I_1") (pintype "input"))
    )
    (net (code "297") (name "~{BUSACK}") (class "Default")
      (node (ref "U10") (pin "10") (pinfunction "PRE_10") (pintype "input"))
      (node (ref "U8") (pin "13") (pinfunction "A2_13") (pintype "input"))
      (node (ref "U9") (pin "10") (pinfunction "PRE_10") (pintype "input"))
      (node (ref "U9") (pin "6") (pinfunction "~{Q}_6") (pintype "output"))
    )
    (net (code "298") (name "~{BWAIT}") (class "Default")
      (node (ref "PC0") (pin "18") (pinfunction "~{WAIT}_18") (pintype "bidirectional"))
      (node (ref "U31") (pin "13") (pinfunction "I_13") (pintype "input"))
    )
    (net (code "299") (name "~{BWR}") (class "Default")
      (node (ref "PC0") (pin "22") (pinfunction "~{WR}_22") (pintype "bidirectional"))
      (node (ref "U2") (pin "3") (pinfunction "C_3") (pintype "input"))
      (node (ref "U8") (pin "16") (pinfunction "Y2_16") (pintype "tri_state"))
    )
    (net (code "300") (name "~{CS0_READ}") (class "Default")
      (node (ref "U12") (pin "1") (pinfunction "G_1") (pintype "input"))
      (node (ref "U12") (pin "19") (pinfunction "G_19") (pintype "input"))
      (node (ref "U2") (pin "11") (pinfunction "Y4_11") (pintype "output"))
    )
    (net (code "301") (name "~{CS0_WRITE}") (class "Default")
      (node (ref "U10") (pin "3") (pinfunction "CLK_3") (pintype "input"))
      (node (ref "U11") (pin "11") (pinfunction "CLK_11") (pintype "input"))
      (node (ref "U2") (pin "13") (pinfunction "Y2_13") (pintype "output"))
    )
    (net (code "302") (name "~{CS1_READ}") (class "Default")
      (node (ref "U18") (pin "4") (pinfunction "I0_4") (pintype "input"))
      (node (ref "U2") (pin "10") (pinfunction "Y5_10") (pintype "output"))
      (node (ref "U21") (pin "1") (pinfunction "G_1") (pintype "input"))
      (node (ref "U21") (pin "19") (pinfunction "G_19") (pintype "input"))
    )
    (net (code "303") (name "~{CS1_WRITE}") (class "Default")
      (node (ref "U2") (pin "12") (pinfunction "Y3_12") (pintype "output"))
      (node (ref "U26") (pin "11") (pinfunction "CLK_11") (pintype "input"))
    )
    (net (code "304") (name "~{HALT}") (class "Default")
      (node (ref "R2") (pin "1") (pinfunction "1_1") (pintype "passive"))
      (node (ref "U17") (pin "8") (pinfunction "O_8") (pintype "output"))
      (node (ref "U8") (pin "15") (pinfunction "A3_15") (pintype "input"))
    )
    (net (code "305") (name "~{IOSEL}") (class "Default")
      (node (ref "U25") (pin "2") (pinfunction "A1_2") (pintype "input"))
      (node (ref "U6") (pin "19") (pinfunction "P=Q_19") (pintype "output"))
    )
    (net (code "306") (name "~{MLB}") (class "Default")
      (node (ref "U18") (pin "2") (pinfunction "I1_2") (pintype "input"))
      (node (ref "U20") (pin "5") (pinfunction "~{MLB}_5") (pintype "output"))
    )
    (net (code "307") (name "~{RD}") (class "Default")
      (node (ref "U17") (pin "3") (pinfunction "O_3") (pintype "output"))
      (node (ref "U22") (pin "5") (pinfunction "G2B_5") (pintype "input"))
      (node (ref "U8") (pin "2") (pinfunction "A1_2") (pintype "input"))
    )
    (net (code "308") (name "~{RST}") (class "Default")
      (node (ref "U10") (pin "4") (pinfunction "PRE_4") (pintype "input"))
      (node (ref "U11") (pin "1") (pinfunction "CLR_1") (pintype "input"))
      (node (ref "U18") (pin "5") (pinfunction "I1_5") (pintype "input"))
      (node (ref "U20") (pin "40") (pinfunction "~{RESB}_40") (pintype "input"))
      (node (ref "U26") (pin "1") (pinfunction "CLR_1") (pintype "input"))
      (node (ref "U31") (pin "4") (pinfunction "O_4") (pintype "output"))
      (node (ref "U9") (pin "1") (pinfunction "CLR_1") (pintype "input"))
      (node (ref "U9") (pin "13") (pinfunction "CLR_13") (pintype "input"))
    )
    (net (code "309") (name "~{VINT}") (class "Default")
      (node (ref "U18") (pin "9") (pinfunction "I0_9") (pintype "input"))
      (node (ref "U23") (pin "14") (pinfunction "GS_14") (pintype "output"))
    )
    (net (code "310") (name "~{VPB}") (class "Default")
      (node (ref "JP3") (pin "2") (pinfunction "2_2") (pintype "passive"))
      (node (ref "U19") (pin "5") (pinfunction "I_5") (pintype "input"))
      (node (ref "U20") (pin "1") (pinfunction "~{VPB}_1") (pintype "output"))
      (node (ref "U22") (pin "4") (pinfunction "G2A_4") (pintype "input"))
    )
    (net (code "311") (name "~{WAIT_DMA}") (class "Default")
      (node (ref "R7") (pin "2") (pinfunction "2_2") (pintype "passive"))
      (node (ref "U17") (pin "9") (pinfunction "I0_9") (pintype "input"))
      (node (ref "U9") (pin "8") (pinfunction "~{Q}_8") (pintype "output"))
    )
    (net (code "312") (name "~{WR}") (class "Default")
      (node (ref "U17") (pin "6") (pinfunction "O_6") (pintype "output"))
      (node (ref "U8") (pin "4") (pinfunction "A2_4") (pintype "input"))
    )
  )
)
